# RK05ex6x10.net
KiCad netlist of a schematic drawn in EAGLE
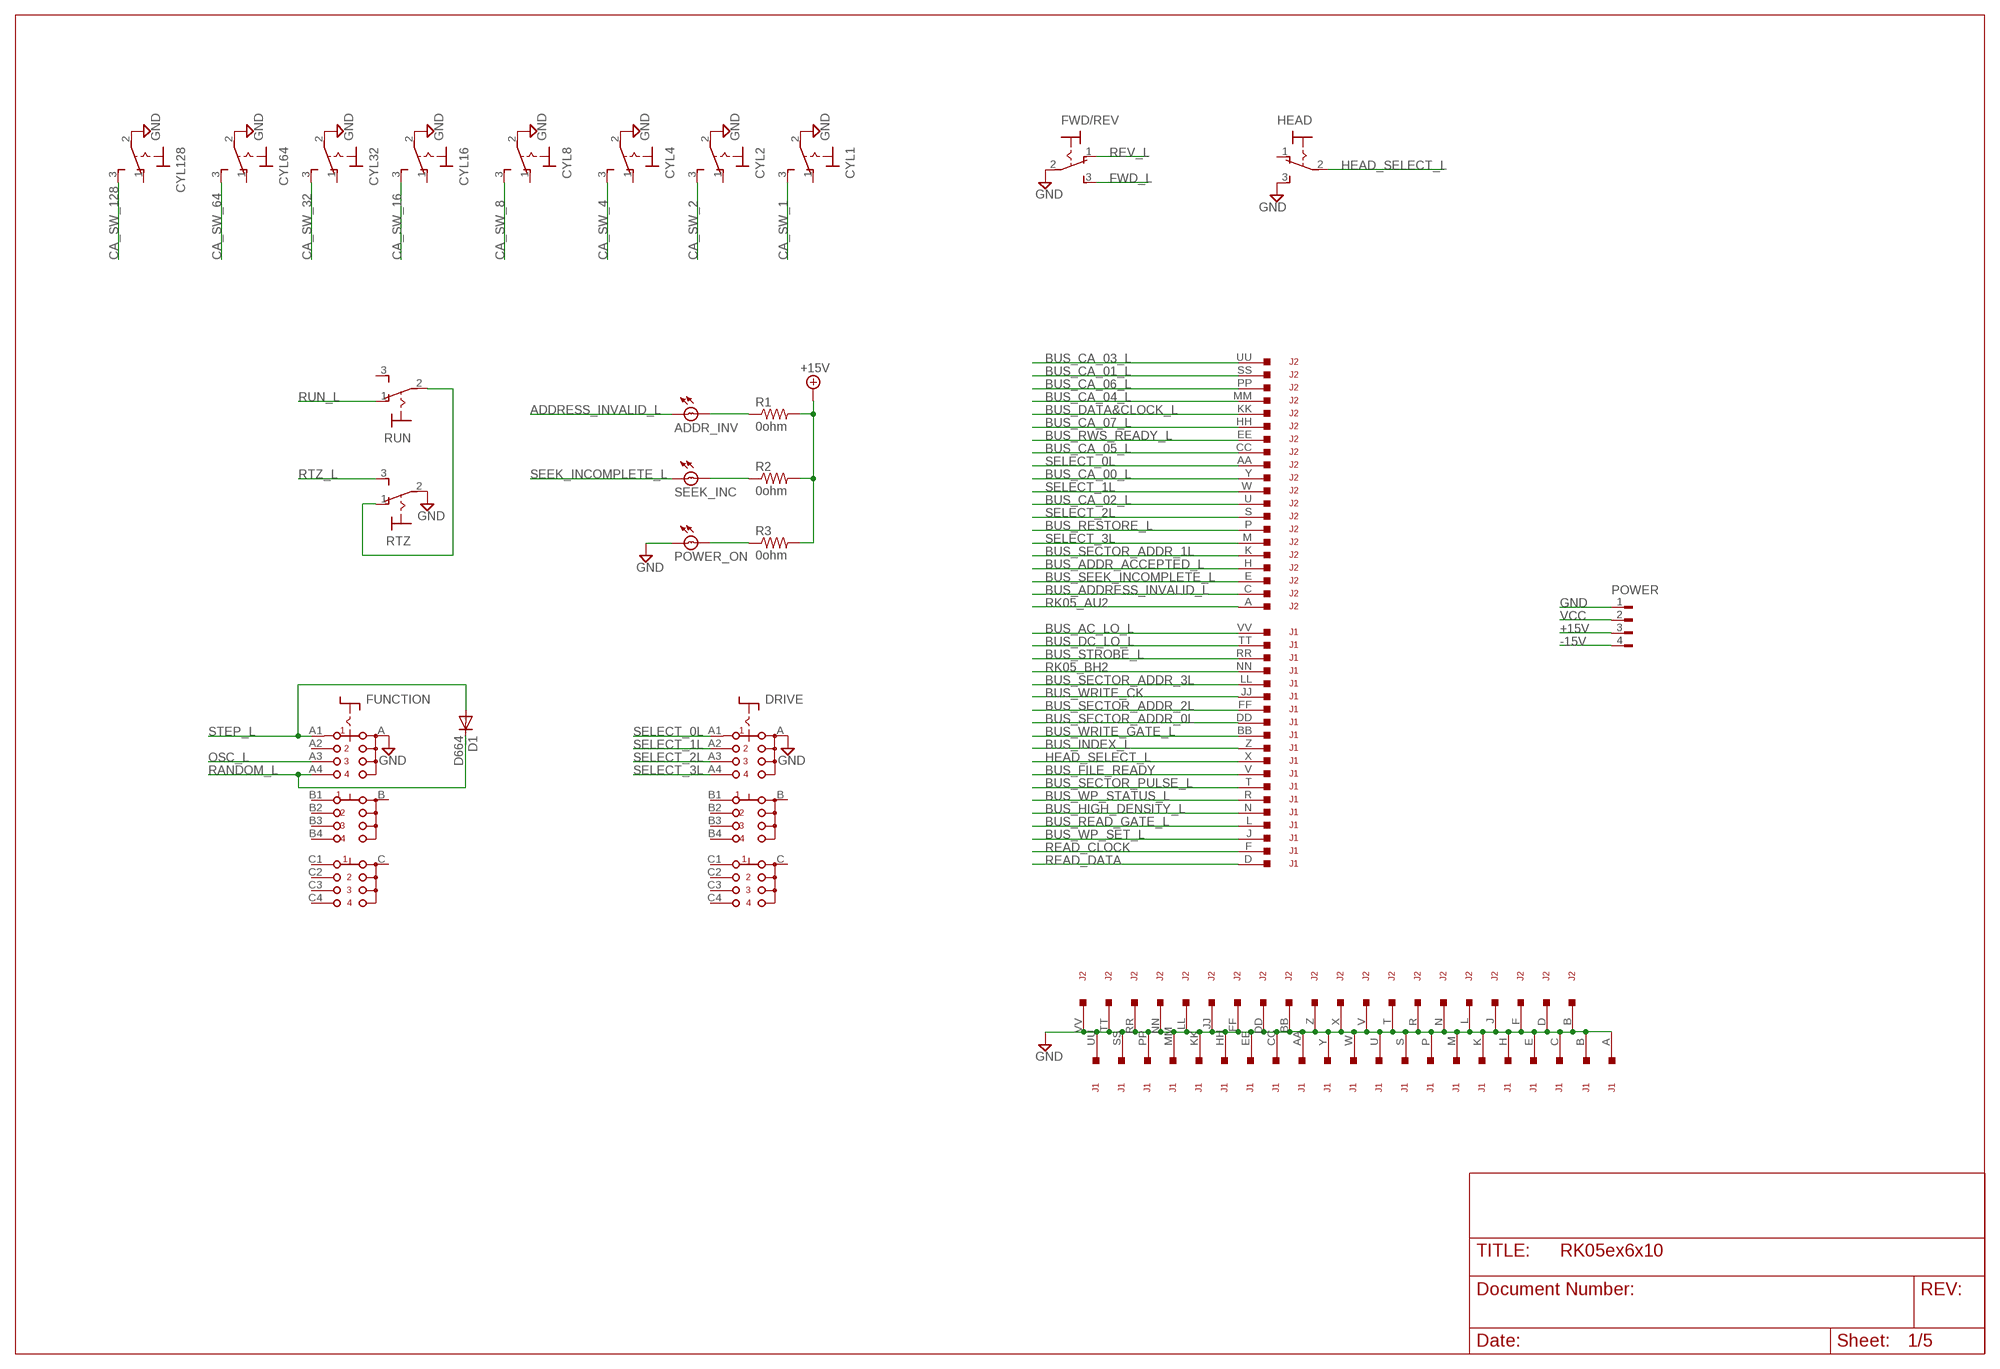
[diagram p0: schematic, sheet 1]
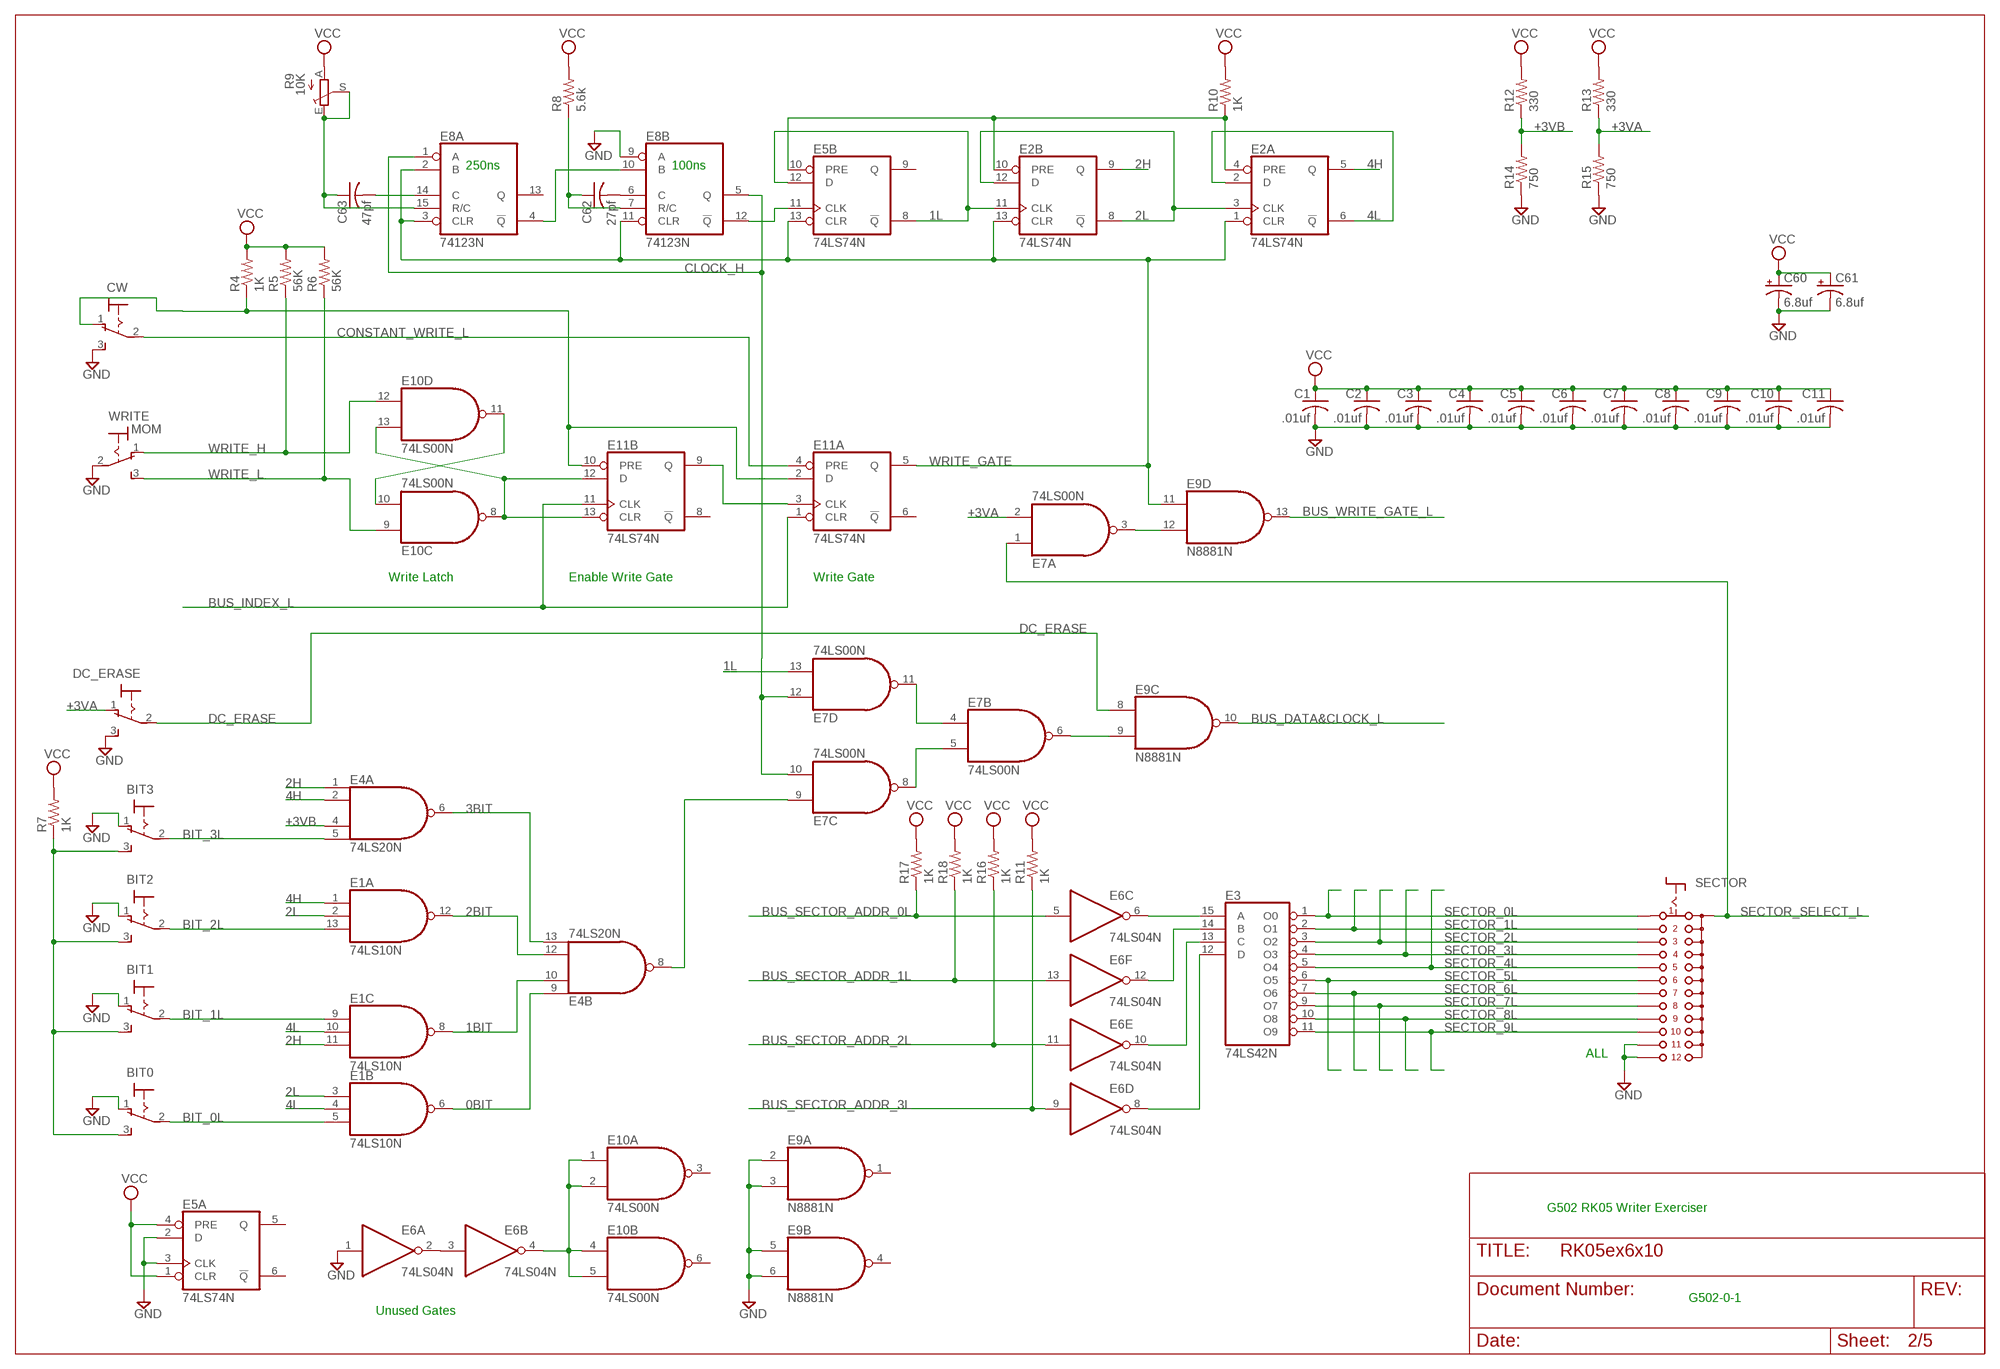
[diagram p1: schematic, sheet 2]
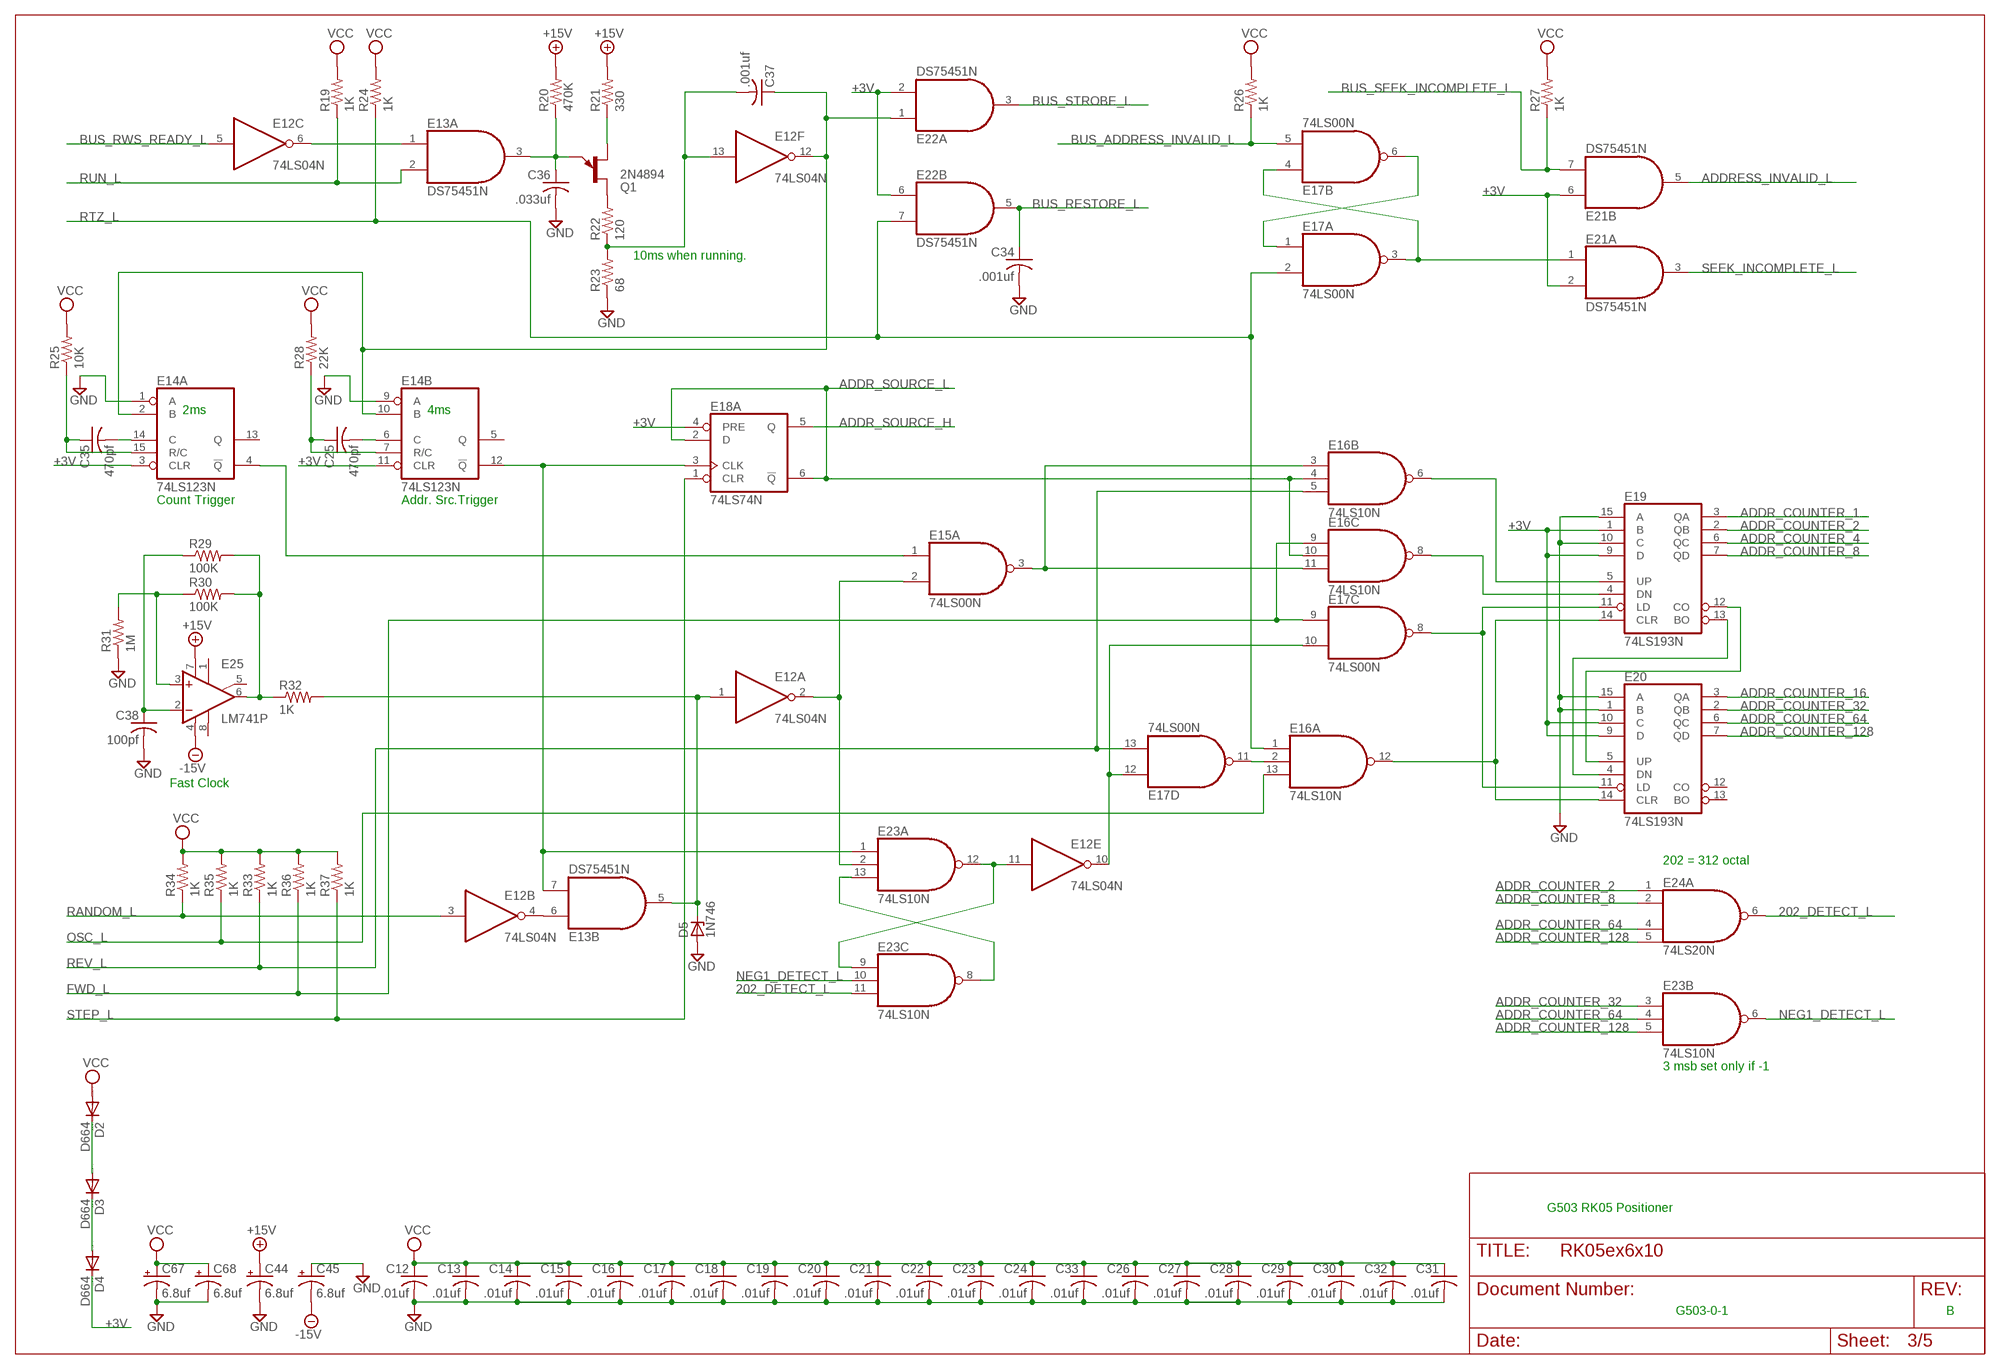
[diagram p2: schematic, sheet 3]
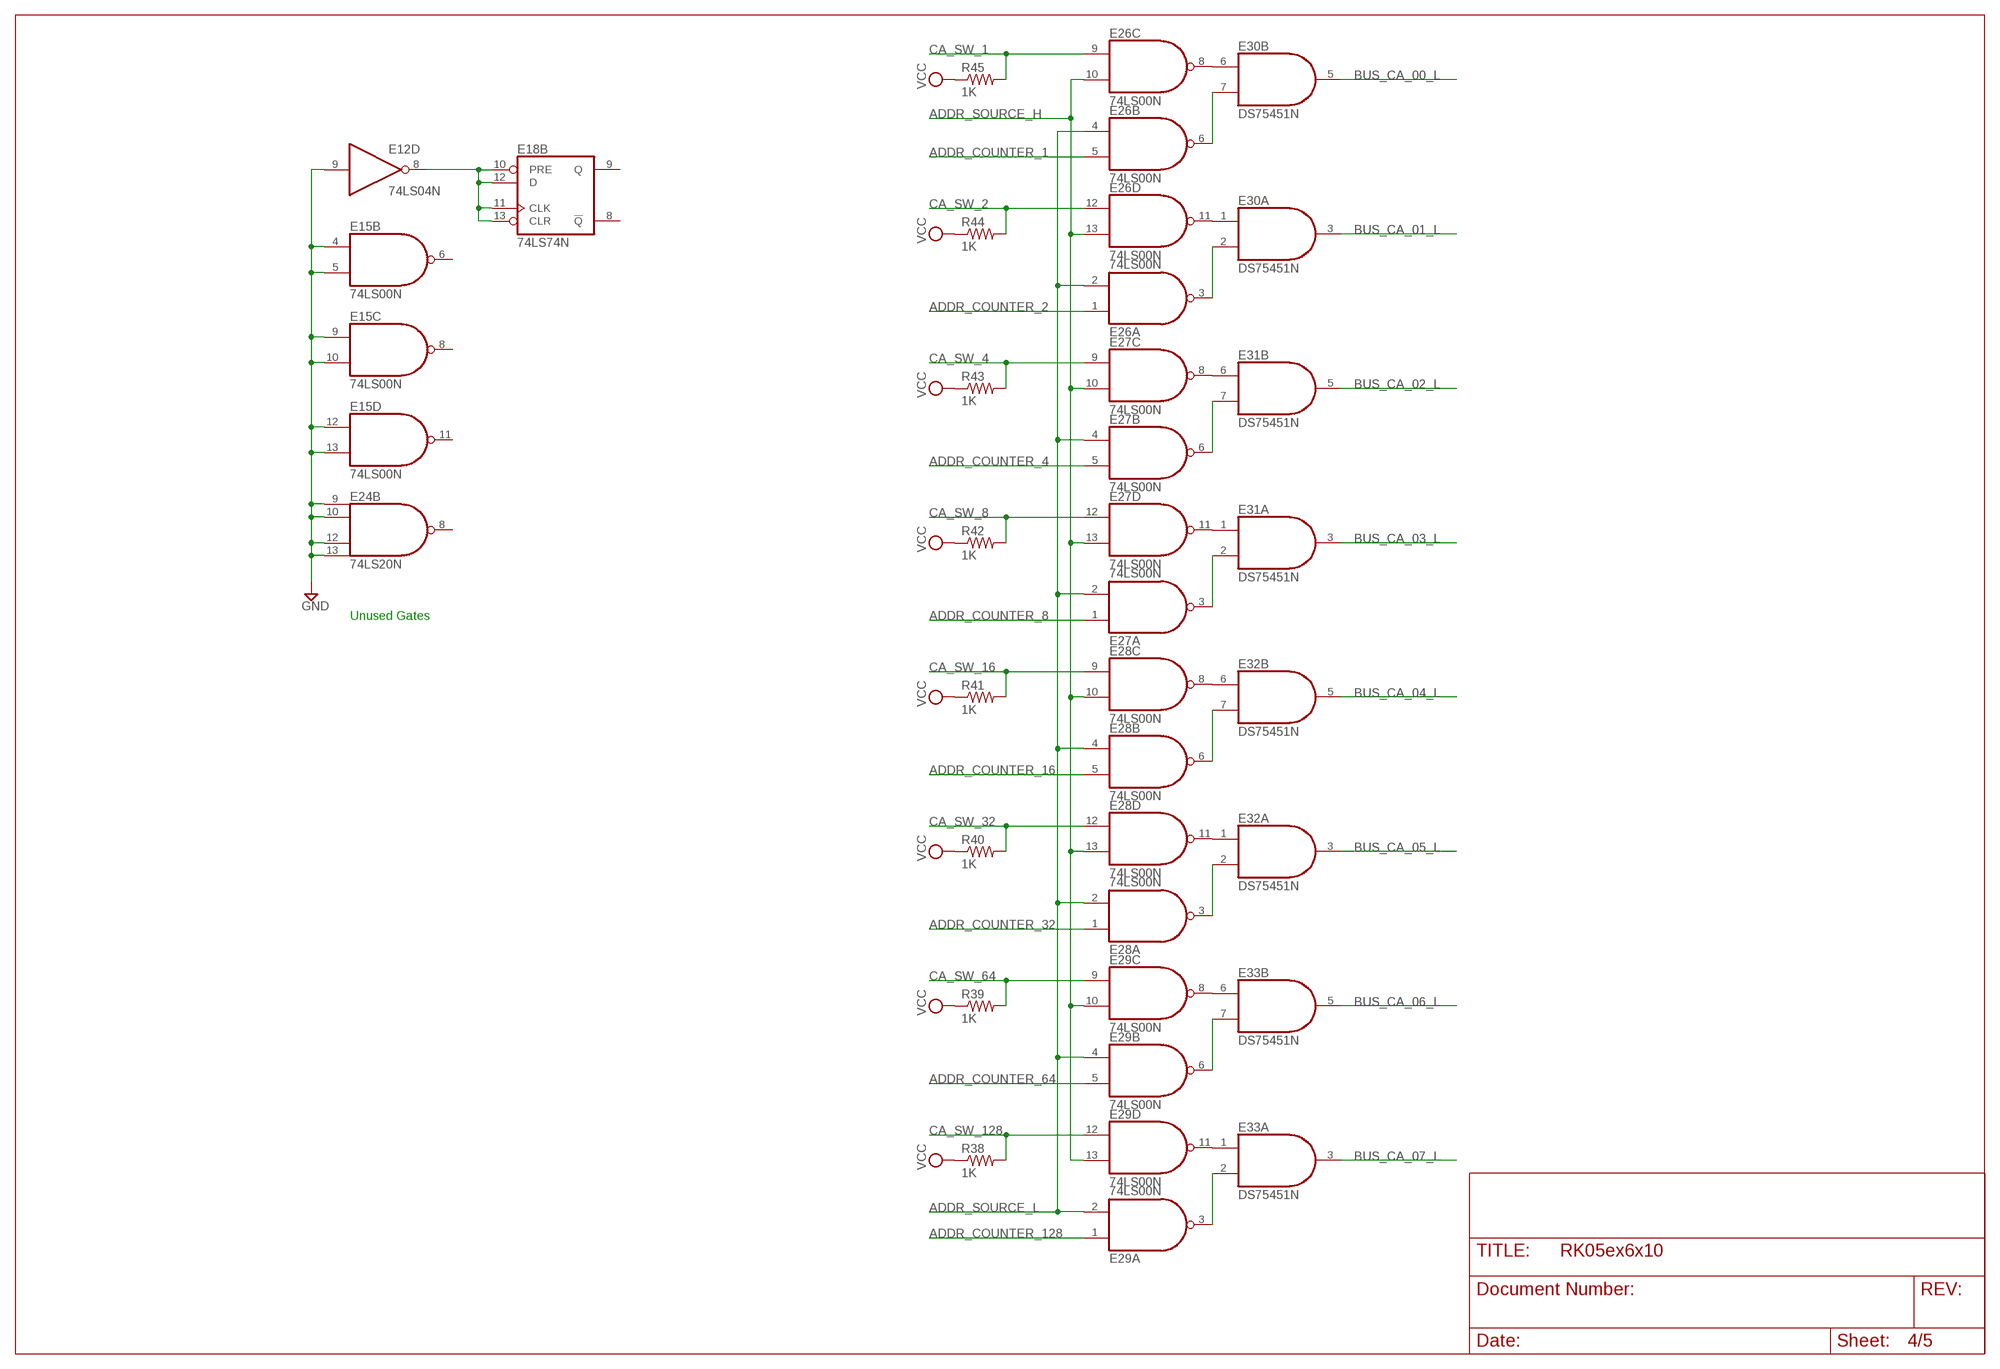
[diagram p3: schematic, sheet 4]
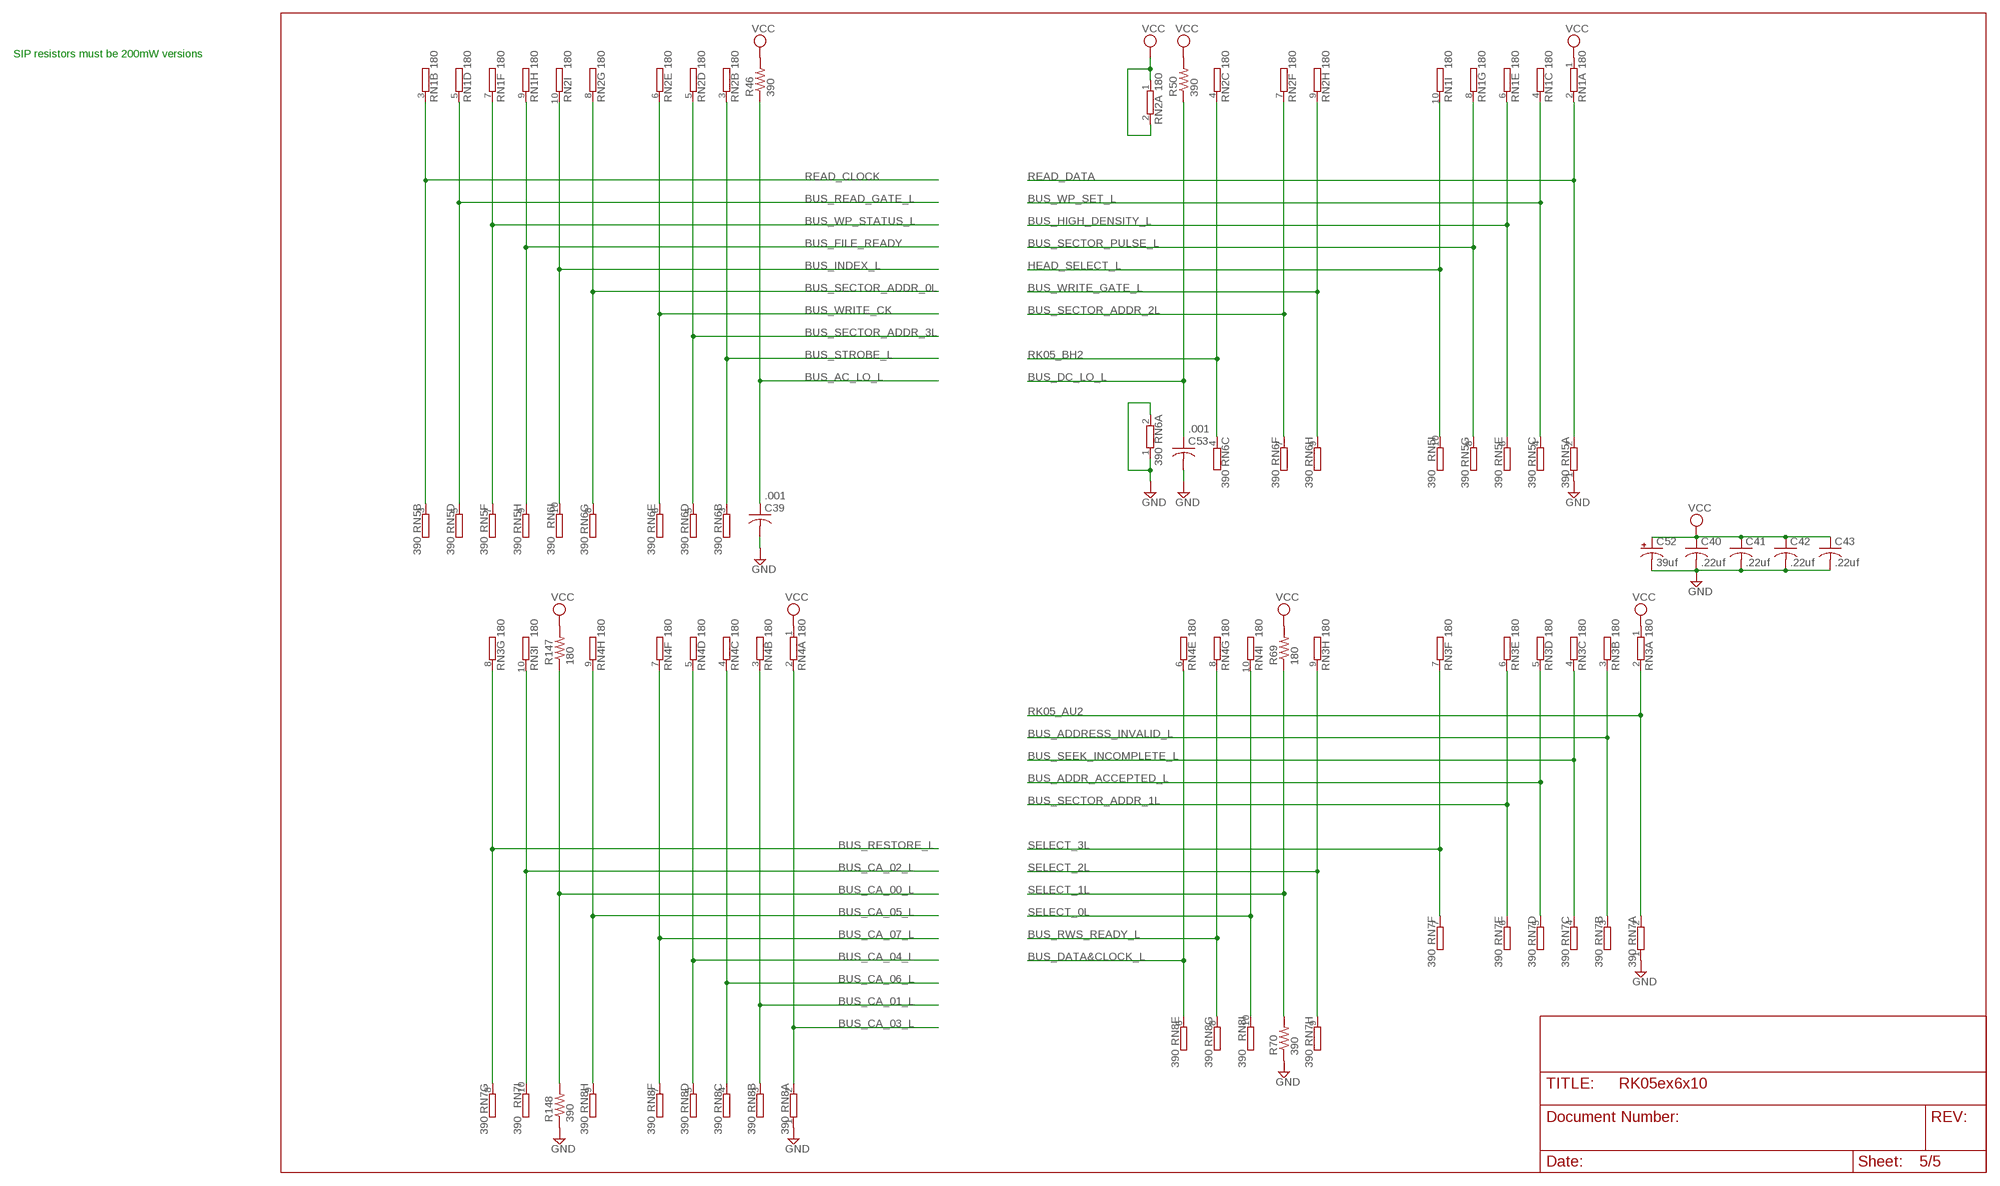
[diagram p4: schematic, sheet 5]

(export (version "E")
  (design (tool "Eeschema 10.0.6"))
  (components
    (comp (ref "BIT0")
      (value "M9040P")
      (footprint "eagle-import:M9040P")
      (libsource (lib "eagle-import") (part "M9040P"))
    )
    (comp (ref "BIT1")
      (value "M9040P")
      (footprint "eagle-import:M9040P")
      (libsource (lib "eagle-import") (part "M9040P"))
    )
    (comp (ref "BIT2")
      (value "M9040P")
      (footprint "eagle-import:M9040P")
      (libsource (lib "eagle-import") (part "M9040P"))
    )
    (comp (ref "BIT3")
      (value "M9040P")
      (footprint "eagle-import:M9040P")
      (libsource (lib "eagle-import") (part "M9040P"))
    )
    (comp (ref "C1")
      (value ".01uf")
      (footprint "eagle-import:C075-032X103")
      (libsource (lib "eagle-import") (part "C-US075-032X103"))
    )
    (comp (ref "C2")
      (value ".01uf")
      (footprint "eagle-import:C075-032X103")
      (libsource (lib "eagle-import") (part "C-US075-032X103"))
    )
    (comp (ref "C3")
      (value ".01uf")
      (footprint "eagle-import:C075-032X103")
      (libsource (lib "eagle-import") (part "C-US075-032X103"))
    )
    (comp (ref "C4")
      (value ".01uf")
      (footprint "eagle-import:C075-032X103")
      (libsource (lib "eagle-import") (part "C-US075-032X103"))
    )
    (comp (ref "C5")
      (value ".01uf")
      (footprint "eagle-import:C075-032X103")
      (libsource (lib "eagle-import") (part "C-US075-032X103"))
    )
    (comp (ref "C6")
      (value ".01uf")
      (footprint "eagle-import:C075-032X103")
      (libsource (lib "eagle-import") (part "C-US075-032X103"))
    )
    (comp (ref "C7")
      (value ".01uf")
      (footprint "eagle-import:C075-032X103")
      (libsource (lib "eagle-import") (part "C-US075-032X103"))
    )
    (comp (ref "C8")
      (value ".01uf")
      (footprint "eagle-import:C075-032X103")
      (libsource (lib "eagle-import") (part "C-US075-032X103"))
    )
    (comp (ref "C9")
      (value ".01uf")
      (footprint "eagle-import:C075-032X103")
      (libsource (lib "eagle-import") (part "C-US075-032X103"))
    )
    (comp (ref "C10")
      (value ".01uf")
      (footprint "eagle-import:C075-032X103")
      (libsource (lib "eagle-import") (part "C-US075-032X103"))
    )
    (comp (ref "C11")
      (value ".01uf")
      (footprint "eagle-import:C075-032X103")
      (libsource (lib "eagle-import") (part "C-US075-032X103"))
    )
    (comp (ref "C60")
      (value "6.8uf")
      (footprint "eagle-import:E15-5")
      (libsource (lib "eagle-import") (part "CPOL-USE15-5AXIAL"))
    )
    (comp (ref "C61")
      (value "6.8uf")
      (footprint "eagle-import:E15-5")
      (libsource (lib "eagle-import") (part "CPOL-USE15-5AXIAL"))
    )
    (comp (ref "C62")
      (value "27pf")
      (footprint "eagle-import:C075-032X103")
      (libsource (lib "eagle-import") (part "C-US075-032X103"))
    )
    (comp (ref "C63")
      (value "47pf")
      (footprint "eagle-import:C075-032X103")
      (libsource (lib "eagle-import") (part "C-US075-032X103"))
    )
    (comp (ref "CW")
      (value "M9040P")
      (footprint "eagle-import:M9040P")
      (libsource (lib "eagle-import") (part "M9040P"))
    )
    (comp (ref "DC_ERASE")
      (value "M9040P")
      (footprint "eagle-import:M9040P")
      (libsource (lib "eagle-import") (part "M9040P"))
    )
    (comp (ref "E1")
      (value "74LS10N")
      (footprint "eagle-import:DIL14")
      (libsource (lib "eagle-import") (part "7410NLS"))
    )
    (comp (ref "E2")
      (value "74LS74N")
      (footprint "eagle-import:DIL14")
      (libsource (lib "eagle-import") (part "7474NLS"))
    )
    (comp (ref "E3")
      (value "74LS42N")
      (footprint "eagle-import:DIL16")
      (libsource (lib "eagle-import") (part "7442NLS"))
    )
    (comp (ref "E4")
      (value "74LS20N")
      (footprint "eagle-import:DIL14")
      (libsource (lib "eagle-import") (part "7420NLS"))
    )
    (comp (ref "E5")
      (value "74LS74N")
      (footprint "eagle-import:DIL14")
      (libsource (lib "eagle-import") (part "7474NLS"))
    )
    (comp (ref "E6")
      (value "74LS04N")
      (footprint "eagle-import:DIL14")
      (libsource (lib "eagle-import") (part "7404NLS"))
    )
    (comp (ref "E7")
      (value "74LS00N")
      (footprint "eagle-import:DIL14")
      (libsource (lib "eagle-import") (part "7400NLS"))
    )
    (comp (ref "E8")
      (value "74123N")
      (footprint "eagle-import:DIL16")
      (libsource (lib "eagle-import") (part "74123NLS"))
    )
    (comp (ref "E9")
      (value "N8881N")
      (footprint "eagle-import:DIL14")
      (libsource (lib "eagle-import") (part "N8881N"))
    )
    (comp (ref "E10")
      (value "74LS00N")
      (footprint "eagle-import:DIL14")
      (libsource (lib "eagle-import") (part "7400NLS"))
    )
    (comp (ref "E11")
      (value "74LS74N")
      (footprint "eagle-import:DIL14")
      (libsource (lib "eagle-import") (part "7474NLS"))
    )
    (comp (ref "R4")
      (value "1K")
      (footprint "eagle-import:0207_10")
      (libsource (lib "eagle-import") (part "R-US_0207/10"))
    )
    (comp (ref "R5")
      (value "56K")
      (footprint "eagle-import:0207_10")
      (libsource (lib "eagle-import") (part "R-US_0207/10"))
    )
    (comp (ref "R6")
      (value "56K")
      (footprint "eagle-import:0207_10")
      (libsource (lib "eagle-import") (part "R-US_0207/10"))
    )
    (comp (ref "R7")
      (value "1K")
      (footprint "eagle-import:0207_10")
      (libsource (lib "eagle-import") (part "R-US_0207/10"))
    )
    (comp (ref "R8")
      (value "5.6k")
      (footprint "eagle-import:0207_10")
      (libsource (lib "eagle-import") (part "R-US_0207/10"))
    )
    (comp (ref "R9")
      (value "10K")
      (footprint "eagle-import:SP19L")
      (libsource (lib "eagle-import") (part "TRIM_EU-B90P"))
    )
    (comp (ref "R10")
      (value "1K")
      (footprint "eagle-import:0207_10")
      (libsource (lib "eagle-import") (part "R-US_0207/10"))
    )
    (comp (ref "R11")
      (value "1K")
      (footprint "eagle-import:0207_10")
      (libsource (lib "eagle-import") (part "R-US_0207/10"))
    )
    (comp (ref "R12")
      (value "330")
      (footprint "eagle-import:0207_10")
      (libsource (lib "eagle-import") (part "R-US_0207/10"))
    )
    (comp (ref "R13")
      (value "330")
      (footprint "eagle-import:0207_10")
      (libsource (lib "eagle-import") (part "R-US_0207/10"))
    )
    (comp (ref "R14")
      (value "750")
      (footprint "eagle-import:0207_10")
      (libsource (lib "eagle-import") (part "R-US_0207/10"))
    )
    (comp (ref "R15")
      (value "750")
      (footprint "eagle-import:0207_10")
      (libsource (lib "eagle-import") (part "R-US_0207/10"))
    )
    (comp (ref "R16")
      (value "1K")
      (footprint "eagle-import:0207_10")
      (libsource (lib "eagle-import") (part "R-US_0207/10"))
    )
    (comp (ref "R17")
      (value "1K")
      (footprint "eagle-import:0207_10")
      (libsource (lib "eagle-import") (part "R-US_0207/10"))
    )
    (comp (ref "R18")
      (value "1K")
      (footprint "eagle-import:0207_10")
      (libsource (lib "eagle-import") (part "R-US_0207/10"))
    )
    (comp (ref "SECTOR")
      (value "CK101X12")
      (footprint "eagle-import:CK101X12")
      (libsource (lib "eagle-import") (part "CK101X12"))
    )
    (comp (ref "WRITE")
      (value "MOM")
      (footprint "eagle-import:M9040P")
      (libsource (lib "eagle-import") (part "M9040P"))
    )
    (comp (ref "C12")
      (value ".01uf")
      (footprint "eagle-import:C075-032X103")
      (libsource (lib "eagle-import") (part "C-US075-032X103"))
    )
    (comp (ref "C13")
      (value ".01uf")
      (footprint "eagle-import:C075-032X103")
      (libsource (lib "eagle-import") (part "C-US075-032X103"))
    )
    (comp (ref "C14")
      (value ".01uf")
      (footprint "eagle-import:C075-032X103")
      (libsource (lib "eagle-import") (part "C-US075-032X103"))
    )
    (comp (ref "C15")
      (value ".01uf")
      (footprint "eagle-import:C075-032X103")
      (libsource (lib "eagle-import") (part "C-US075-032X103"))
    )
    (comp (ref "C16")
      (value ".01uf")
      (footprint "eagle-import:C075-032X103")
      (libsource (lib "eagle-import") (part "C-US075-032X103"))
    )
    (comp (ref "C17")
      (value ".01uf")
      (footprint "eagle-import:C075-032X103")
      (libsource (lib "eagle-import") (part "C-US075-032X103"))
    )
    (comp (ref "C18")
      (value ".01uf")
      (footprint "eagle-import:C075-032X103")
      (libsource (lib "eagle-import") (part "C-US075-032X103"))
    )
    (comp (ref "C19")
      (value ".01uf")
      (footprint "eagle-import:C075-032X103")
      (libsource (lib "eagle-import") (part "C-US075-032X103"))
    )
    (comp (ref "C20")
      (value ".01uf")
      (footprint "eagle-import:C075-032X103")
      (libsource (lib "eagle-import") (part "C-US075-032X103"))
    )
    (comp (ref "C21")
      (value ".01uf")
      (footprint "eagle-import:C075-032X103")
      (libsource (lib "eagle-import") (part "C-US075-032X103"))
    )
    (comp (ref "C22")
      (value ".01uf")
      (footprint "eagle-import:C075-032X103")
      (libsource (lib "eagle-import") (part "C-US075-032X103"))
    )
    (comp (ref "C23")
      (value ".01uf")
      (footprint "eagle-import:C075-032X103")
      (libsource (lib "eagle-import") (part "C-US075-032X103"))
    )
    (comp (ref "C24")
      (value ".01uf")
      (footprint "eagle-import:C075-032X103")
      (libsource (lib "eagle-import") (part "C-US075-032X103"))
    )
    (comp (ref "C25")
      (value "470pf")
      (footprint "eagle-import:C075-032X103")
      (libsource (lib "eagle-import") (part "C-US075-032X103"))
    )
    (comp (ref "C26")
      (value ".01uf")
      (footprint "eagle-import:C075-032X103")
      (libsource (lib "eagle-import") (part "C-US075-032X103"))
    )
    (comp (ref "C27")
      (value ".01uf")
      (footprint "eagle-import:C075-032X103")
      (libsource (lib "eagle-import") (part "C-US075-032X103"))
    )
    (comp (ref "C28")
      (value ".01uf")
      (footprint "eagle-import:C075-032X103")
      (libsource (lib "eagle-import") (part "C-US075-032X103"))
    )
    (comp (ref "C29")
      (value ".01uf")
      (footprint "eagle-import:C075-032X103")
      (libsource (lib "eagle-import") (part "C-US075-032X103"))
    )
    (comp (ref "C30")
      (value ".01uf")
      (footprint "eagle-import:C075-032X103")
      (libsource (lib "eagle-import") (part "C-US075-032X103"))
    )
    (comp (ref "C31")
      (value ".01uf")
      (footprint "eagle-import:C075-032X103")
      (libsource (lib "eagle-import") (part "C-US075-032X103"))
    )
    (comp (ref "C32")
      (value ".01uf")
      (footprint "eagle-import:C075-032X103")
      (libsource (lib "eagle-import") (part "C-US075-032X103"))
    )
    (comp (ref "C33")
      (value ".01uf")
      (footprint "eagle-import:C075-032X103")
      (libsource (lib "eagle-import") (part "C-US075-032X103"))
    )
    (comp (ref "C34")
      (value ".001uf")
      (footprint "eagle-import:C075-032X103")
      (libsource (lib "eagle-import") (part "C-US075-032X103"))
    )
    (comp (ref "C35")
      (value "470pf")
      (footprint "eagle-import:C075-032X103")
      (libsource (lib "eagle-import") (part "C-US075-032X103"))
    )
    (comp (ref "C36")
      (value ".033uf")
      (footprint "eagle-import:C075-032X103")
      (libsource (lib "eagle-import") (part "C-US075-032X103"))
    )
    (comp (ref "C37")
      (value ".001uf")
      (footprint "eagle-import:C075-032X103")
      (libsource (lib "eagle-import") (part "C-US075-032X103"))
    )
    (comp (ref "C38")
      (value "100pf")
      (footprint "eagle-import:C075-032X103")
      (libsource (lib "eagle-import") (part "C-US075-032X103"))
    )
    (comp (ref "C44")
      (value "6.8uf")
      (footprint "eagle-import:E15-5")
      (libsource (lib "eagle-import") (part "CPOL-USE15-5AXIAL"))
    )
    (comp (ref "C45")
      (value "6.8uf")
      (footprint "eagle-import:E15-5")
      (libsource (lib "eagle-import") (part "CPOL-USE15-5AXIAL"))
    )
    (comp (ref "C67")
      (value "6.8uf")
      (footprint "eagle-import:E15-5")
      (libsource (lib "eagle-import") (part "CPOL-USE15-5AXIAL"))
    )
    (comp (ref "C68")
      (value "6.8uf")
      (footprint "eagle-import:E15-5")
      (libsource (lib "eagle-import") (part "CPOL-USE15-5AXIAL"))
    )
    (comp (ref "D2")
      (value "D664")
      (footprint "eagle-import:DO35-10")
      (libsource (lib "eagle-import") (part "1N4148DO35-10"))
    )
    (comp (ref "D3")
      (value "D664")
      (footprint "eagle-import:DO35-10")
      (libsource (lib "eagle-import") (part "1N4148DO35-10"))
    )
    (comp (ref "D4")
      (value "D664")
      (footprint "eagle-import:DO35-10")
      (libsource (lib "eagle-import") (part "1N4148DO35-10"))
    )
    (comp (ref "D5")
      (value "1N746")
      (footprint "eagle-import:DO35Z10")
      (libsource (lib "eagle-import") (part "ZENER-DIODEDO35Z10"))
    )
    (comp (ref "E12")
      (value "74LS04N")
      (footprint "eagle-import:DIL14")
      (libsource (lib "eagle-import") (part "7404NLS"))
    )
    (comp (ref "E13")
      (value "DS75451N")
      (footprint "eagle-import:DIL08")
      (libsource (lib "eagle-import") (part "DS75451N"))
    )
    (comp (ref "E14")
      (value "74LS123N")
      (footprint "eagle-import:DIL16")
      (libsource (lib "eagle-import") (part "74123NLS"))
    )
    (comp (ref "E15")
      (value "74LS00N")
      (footprint "eagle-import:DIL14")
      (libsource (lib "eagle-import") (part "7400NLS"))
    )
    (comp (ref "E16")
      (value "74LS10N")
      (footprint "eagle-import:DIL14")
      (libsource (lib "eagle-import") (part "7410NAS"))
    )
    (comp (ref "E17")
      (value "74LS00N")
      (footprint "eagle-import:DIL14")
      (libsource (lib "eagle-import") (part "7400NLS"))
    )
    (comp (ref "E18")
      (value "74LS74N")
      (footprint "eagle-import:DIL14")
      (libsource (lib "eagle-import") (part "7474NLS"))
    )
    (comp (ref "E19")
      (value "74LS193N")
      (footprint "eagle-import:DIL16")
      (libsource (lib "eagle-import") (part "74193NLS"))
    )
    (comp (ref "E20")
      (value "74LS193N")
      (footprint "eagle-import:DIL16")
      (libsource (lib "eagle-import") (part "74193NLS"))
    )
    (comp (ref "E21")
      (value "DS75451N")
      (footprint "eagle-import:DIL08")
      (libsource (lib "eagle-import") (part "DS75451N"))
    )
    (comp (ref "E22")
      (value "DS75451N")
      (footprint "eagle-import:DIL08")
      (libsource (lib "eagle-import") (part "DS75451N"))
    )
    (comp (ref "E23")
      (value "74LS10N")
      (footprint "eagle-import:DIL14")
      (libsource (lib "eagle-import") (part "7410NAS"))
    )
    (comp (ref "E24")
      (value "74LS20N")
      (footprint "eagle-import:DIL14")
      (libsource (lib "eagle-import") (part "7420NLS"))
    )
    (comp (ref "E25")
      (value "LM741P")
      (footprint "eagle-import:DIL08")
      (libsource (lib "eagle-import") (part "741PLM"))
    )
    (comp (ref "Q1")
      (value "2N4894")
      (footprint "eagle-import:TO92E")
      (libsource (lib "eagle-import") (part "2N4870"))
    )
    (comp (ref "R19")
      (value "1K")
      (footprint "eagle-import:0207_10")
      (libsource (lib "eagle-import") (part "R-US_0207/10"))
    )
    (comp (ref "R20")
      (value "470K")
      (footprint "eagle-import:0207_10")
      (libsource (lib "eagle-import") (part "R-US_0207/10"))
    )
    (comp (ref "R21")
      (value "330")
      (footprint "eagle-import:0207_10")
      (libsource (lib "eagle-import") (part "R-US_0207/10"))
    )
    (comp (ref "R22")
      (value "120")
      (footprint "eagle-import:0207_10")
      (libsource (lib "eagle-import") (part "R-US_0207/10"))
    )
    (comp (ref "R23")
      (value "68")
      (footprint "eagle-import:0207_10")
      (libsource (lib "eagle-import") (part "R-US_0207/10"))
    )
    (comp (ref "R24")
      (value "1K")
      (footprint "eagle-import:0207_10")
      (libsource (lib "eagle-import") (part "R-US_0207/10"))
    )
    (comp (ref "R25")
      (value "10K")
      (footprint "eagle-import:0207_10")
      (libsource (lib "eagle-import") (part "R-US_0207/10"))
    )
    (comp (ref "R26")
      (value "1K")
      (footprint "eagle-import:0207_10")
      (libsource (lib "eagle-import") (part "R-US_0207/10"))
    )
    (comp (ref "R27")
      (value "1K")
      (footprint "eagle-import:0207_10")
      (libsource (lib "eagle-import") (part "R-US_0207/10"))
    )
    (comp (ref "R28")
      (value "22K")
      (footprint "eagle-import:0207_10")
      (libsource (lib "eagle-import") (part "R-US_0207/10"))
    )
    (comp (ref "R29")
      (value "100K")
      (footprint "eagle-import:0207_10")
      (libsource (lib "eagle-import") (part "R-US_0207/10"))
    )
    (comp (ref "R30")
      (value "100K")
      (footprint "eagle-import:0207_10")
      (libsource (lib "eagle-import") (part "R-US_0207/10"))
    )
    (comp (ref "R31")
      (value "1M")
      (footprint "eagle-import:0207_10")
      (libsource (lib "eagle-import") (part "R-US_0207/10"))
    )
    (comp (ref "R32")
      (value "1K")
      (footprint "eagle-import:0207_10")
      (libsource (lib "eagle-import") (part "R-US_0207/10"))
    )
    (comp (ref "R33")
      (value "1K")
      (footprint "eagle-import:0207_10")
      (libsource (lib "eagle-import") (part "R-US_0207/10"))
    )
    (comp (ref "R34")
      (value "1K")
      (footprint "eagle-import:0207_10")
      (libsource (lib "eagle-import") (part "R-US_0207/10"))
    )
    (comp (ref "R35")
      (value "1K")
      (footprint "eagle-import:0207_10")
      (libsource (lib "eagle-import") (part "R-US_0207/10"))
    )
    (comp (ref "R36")
      (value "1K")
      (footprint "eagle-import:0207_10")
      (libsource (lib "eagle-import") (part "R-US_0207/10"))
    )
    (comp (ref "R37")
      (value "1K")
      (footprint "eagle-import:0207_10")
      (libsource (lib "eagle-import") (part "R-US_0207/10"))
    )
    (comp (ref "E26")
      (value "74LS00N")
      (footprint "eagle-import:DIL14")
      (libsource (lib "eagle-import") (part "7400NLS"))
    )
    (comp (ref "E27")
      (value "74LS00N")
      (footprint "eagle-import:DIL14")
      (libsource (lib "eagle-import") (part "7400NLS"))
    )
    (comp (ref "E28")
      (value "74LS00N")
      (footprint "eagle-import:DIL14")
      (libsource (lib "eagle-import") (part "7400NLS"))
    )
    (comp (ref "E29")
      (value "74LS00N")
      (footprint "eagle-import:DIL14")
      (libsource (lib "eagle-import") (part "7400NLS"))
    )
    (comp (ref "E30")
      (value "DS75451N")
      (footprint "eagle-import:DIL08")
      (libsource (lib "eagle-import") (part "DS75451N"))
    )
    (comp (ref "E31")
      (value "DS75451N")
      (footprint "eagle-import:DIL08")
      (libsource (lib "eagle-import") (part "DS75451N"))
    )
    (comp (ref "E32")
      (value "DS75451N")
      (footprint "eagle-import:DIL08")
      (libsource (lib "eagle-import") (part "DS75451N"))
    )
    (comp (ref "E33")
      (value "DS75451N")
      (footprint "eagle-import:DIL08")
      (libsource (lib "eagle-import") (part "DS75451N"))
    )
    (comp (ref "R38")
      (value "1K")
      (footprint "eagle-import:0207_10")
      (libsource (lib "eagle-import") (part "R-US_0207/10"))
    )
    (comp (ref "R39")
      (value "1K")
      (footprint "eagle-import:0207_10")
      (libsource (lib "eagle-import") (part "R-US_0207/10"))
    )
    (comp (ref "R40")
      (value "1K")
      (footprint "eagle-import:0207_10")
      (libsource (lib "eagle-import") (part "R-US_0207/10"))
    )
    (comp (ref "R41")
      (value "1K")
      (footprint "eagle-import:0207_10")
      (libsource (lib "eagle-import") (part "R-US_0207/10"))
    )
    (comp (ref "R42")
      (value "1K")
      (footprint "eagle-import:0207_10")
      (libsource (lib "eagle-import") (part "R-US_0207/10"))
    )
    (comp (ref "R43")
      (value "1K")
      (footprint "eagle-import:0207_10")
      (libsource (lib "eagle-import") (part "R-US_0207/10"))
    )
    (comp (ref "R44")
      (value "1K")
      (footprint "eagle-import:0207_10")
      (libsource (lib "eagle-import") (part "R-US_0207/10"))
    )
    (comp (ref "R45")
      (value "1K")
      (footprint "eagle-import:0207_10")
      (libsource (lib "eagle-import") (part "R-US_0207/10"))
    )
    (comp (ref "ADDR_INV")
      (value "BULB")
      (footprint "eagle-import:BULB")
      (libsource (lib "eagle-import") (part "BULB"))
    )
    (comp (ref "CYL1")
      (value "M9040P")
      (footprint "eagle-import:M9040P")
      (libsource (lib "eagle-import") (part "M9040P"))
    )
    (comp (ref "CYL2")
      (value "M9040P")
      (footprint "eagle-import:M9040P")
      (libsource (lib "eagle-import") (part "M9040P"))
    )
    (comp (ref "CYL4")
      (value "M9040P")
      (footprint "eagle-import:M9040P")
      (libsource (lib "eagle-import") (part "M9040P"))
    )
    (comp (ref "CYL8")
      (value "M9040P")
      (footprint "eagle-import:M9040P")
      (libsource (lib "eagle-import") (part "M9040P"))
    )
    (comp (ref "CYL16")
      (value "M9040P")
      (footprint "eagle-import:M9040P")
      (libsource (lib "eagle-import") (part "M9040P"))
    )
    (comp (ref "CYL32")
      (value "M9040P")
      (footprint "eagle-import:M9040P")
      (libsource (lib "eagle-import") (part "M9040P"))
    )
    (comp (ref "CYL64")
      (value "M9040P")
      (footprint "eagle-import:M9040P")
      (libsource (lib "eagle-import") (part "M9040P"))
    )
    (comp (ref "CYL128")
      (value "M9040P")
      (footprint "eagle-import:M9040P")
      (libsource (lib "eagle-import") (part "M9040P"))
    )
    (comp (ref "D1")
      (value "D664")
      (footprint "eagle-import:DO35-10")
      (libsource (lib "eagle-import") (part "1N4148DO35-10"))
    )
    (comp (ref "DRIVE")
      (value "CK103X04")
      (footprint "eagle-import:CK103X04")
      (libsource (lib "eagle-import") (part "CK103X04"))
    )
    (comp (ref "FUNCTION")
      (value "CK103X04")
      (footprint "eagle-import:CK103X04")
      (libsource (lib "eagle-import") (part "CK103X04"))
    )
    (comp (ref "FWD/REV")
      (value "M9040P")
      (footprint "eagle-import:M9040P")
      (libsource (lib "eagle-import") (part "M9040P"))
    )
    (comp (ref "HEAD")
      (value "M9040P")
      (footprint "eagle-import:M9040P")
      (libsource (lib "eagle-import") (part "M9040P"))
    )
    (comp (ref "J1")
      (value "DEC40PINSV")
      (footprint "eagle-import:DEC40PINV")
      (libsource (lib "eagle-import") (part "DEC40PINSV"))
    )
    (comp (ref "J2")
      (value "DEC40PINSV")
      (footprint "eagle-import:DEC40PINV")
      (libsource (lib "eagle-import") (part "DEC40PINSV"))
    )
    (comp (ref "POWER")
      (value "FLOPPY-4")
      (footprint "eagle-import:FLOPPY-4")
      (libsource (lib "eagle-import") (part "FLOPPY-4"))
    )
    (comp (ref "POWER_ON")
      (value "BULB")
      (footprint "eagle-import:BULB")
      (libsource (lib "eagle-import") (part "BULB"))
    )
    (comp (ref "R1")
      (value "0ohm")
      (footprint "eagle-import:0207_10")
      (libsource (lib "eagle-import") (part "R-US_0207/10"))
    )
    (comp (ref "R2")
      (value "0ohm")
      (footprint "eagle-import:0207_10")
      (libsource (lib "eagle-import") (part "R-US_0207/10"))
    )
    (comp (ref "R3")
      (value "0ohm")
      (footprint "eagle-import:0207_10")
      (libsource (lib "eagle-import") (part "R-US_0207/10"))
    )
    (comp (ref "RTZ")
      (value "M9040P")
      (footprint "eagle-import:M9040P")
      (libsource (lib "eagle-import") (part "M9040P"))
    )
    (comp (ref "RUN")
      (value "M9040P")
      (footprint "eagle-import:M9040P")
      (libsource (lib "eagle-import") (part "M9040P"))
    )
    (comp (ref "SEEK_INC")
      (value "BULB")
      (footprint "eagle-import:BULB")
      (libsource (lib "eagle-import") (part "BULB"))
    )
    (comp (ref "C39")
      (value ".001")
      (footprint "eagle-import:C050-025X075")
      (libsource (lib "eagle-import") (part "C-US050-025X075"))
    )
    (comp (ref "C40")
      (value ".22uf")
      (footprint "eagle-import:C050-025X075")
      (libsource (lib "eagle-import") (part "C-US050-025X075"))
    )
    (comp (ref "C41")
      (value ".22uf")
      (footprint "eagle-import:C050-025X075")
      (libsource (lib "eagle-import") (part "C-US050-025X075"))
    )
    (comp (ref "C42")
      (value ".22uf")
      (footprint "eagle-import:C050-025X075")
      (libsource (lib "eagle-import") (part "C-US050-025X075"))
    )
    (comp (ref "C43")
      (value ".22uf")
      (footprint "eagle-import:C050-025X075")
      (libsource (lib "eagle-import") (part "C-US050-025X075"))
    )
    (comp (ref "C52")
      (value "39uf")
      (footprint "eagle-import:E15-5")
      (libsource (lib "eagle-import") (part "CPOL-USE15-5AXIAL"))
    )
    (comp (ref "C53")
      (value ".001")
      (footprint "eagle-import:C050-025X075")
      (libsource (lib "eagle-import") (part "C-US050-025X075"))
    )
    (comp (ref "R46")
      (value "390")
      (footprint "eagle-import:0207_10")
      (libsource (lib "eagle-import") (part "R-US_0207/10"))
    )
    (comp (ref "R50")
      (value "390")
      (footprint "eagle-import:0207_10")
      (libsource (lib "eagle-import") (part "R-US_0207/10"))
    )
    (comp (ref "R69")
      (value "180")
      (footprint "eagle-import:0207_10")
      (libsource (lib "eagle-import") (part "R-US_0207/10"))
    )
    (comp (ref "R70")
      (value "390")
      (footprint "eagle-import:0207_10")
      (libsource (lib "eagle-import") (part "R-US_0207/10"))
    )
    (comp (ref "R147")
      (value "180")
      (footprint "eagle-import:0207_10")
      (libsource (lib "eagle-import") (part "R-US_0207/10"))
    )
    (comp (ref "R148")
      (value "390")
      (footprint "eagle-import:0207_10")
      (libsource (lib "eagle-import") (part "R-US_0207/10"))
    )
    (comp (ref "RN1")
      (value "180")
      (footprint "eagle-import:SIL10")
      (libsource (lib "eagle-import") (part "GE09R"))
    )
    (comp (ref "RN2")
      (value "180")
      (footprint "eagle-import:SIL10")
      (libsource (lib "eagle-import") (part "GE09R"))
    )
    (comp (ref "RN3")
      (value "180")
      (footprint "eagle-import:SIL10")
      (libsource (lib "eagle-import") (part "GE09R"))
    )
    (comp (ref "RN4")
      (value "180")
      (footprint "eagle-import:SIL10")
      (libsource (lib "eagle-import") (part "GE09R"))
    )
    (comp (ref "RN5")
      (value "390")
      (footprint "eagle-import:SIL10")
      (libsource (lib "eagle-import") (part "GE09R"))
    )
    (comp (ref "RN6")
      (value "390")
      (footprint "eagle-import:SIL10")
      (libsource (lib "eagle-import") (part "GE09R"))
    )
    (comp (ref "RN7")
      (value "390")
      (footprint "eagle-import:SIL10")
      (libsource (lib "eagle-import") (part "GE09R"))
    )
    (comp (ref "RN8")
      (value "390")
      (footprint "eagle-import:SIL10")
      (libsource (lib "eagle-import") (part "GE09R"))
    )
  )
  (nets
    (net (code "1") (name "+3V") (class "Default")
      (node (ref "D4") (pin "C") (pinfunction "C_C") (pintype "passive"))
      (node (ref "E14") (pin "11") (pinfunction "CLR_11") (pintype "input"))
      (node (ref "E14") (pin "3") (pinfunction "CLR_3") (pintype "input"))
      (node (ref "E18") (pin "4") (pinfunction "PRE_4") (pintype "input"))
      (node (ref "E19") (pin "1") (pinfunction "B_1") (pintype "input"))
      (node (ref "E19") (pin "9") (pinfunction "D_9") (pintype "input"))
      (node (ref "E20") (pin "10") (pinfunction "C_10") (pintype "input"))
      (node (ref "E20") (pin "9") (pinfunction "D_9") (pintype "input"))
      (node (ref "E21") (pin "2") (pinfunction "I1_2") (pintype "input"))
      (node (ref "E21") (pin "6") (pinfunction "I0_6") (pintype "input"))
      (node (ref "E22") (pin "2") (pinfunction "I1_2") (pintype "input"))
      (node (ref "E22") (pin "6") (pinfunction "I0_6") (pintype "input"))
    )
    (net (code "2") (name "+3VA") (class "Default")
      (node (ref "DC_ERASE") (pin "1") (pinfunction "O_1") (pintype "passive"))
      (node (ref "E7") (pin "2") (pinfunction "I1_2") (pintype "input"))
      (node (ref "R13") (pin "1") (pinfunction "1_1") (pintype "passive"))
      (node (ref "R15") (pin "2") (pinfunction "2_2") (pintype "passive"))
    )
    (net (code "3") (name "+3VB") (class "Default")
      (node (ref "E4") (pin "4") (pinfunction "I2_4") (pintype "input"))
      (node (ref "R12") (pin "1") (pinfunction "1_1") (pintype "passive"))
      (node (ref "R14") (pin "2") (pinfunction "2_2") (pintype "passive"))
    )
    (net (code "4") (name "+15V") (class "Default")
      (node (ref "C44") (pin "+") (pinfunction "+_+") (pintype "passive"))
      (node (ref "E25") (pin "7") (pinfunction "V+_7") (pintype "power_in"))
      (node (ref "POWER") (pin "3") (pinfunction "3_3") (pintype "passive"))
      (node (ref "R1") (pin "2") (pinfunction "2_2") (pintype "passive"))
      (node (ref "R2") (pin "2") (pinfunction "2_2") (pintype "passive"))
      (node (ref "R20") (pin "2") (pinfunction "2_2") (pintype "passive"))
      (node (ref "R21") (pin "2") (pinfunction "2_2") (pintype "passive"))
      (node (ref "R3") (pin "2") (pinfunction "2_2") (pintype "passive"))
    )
    (net (code "5") (name "-15V") (class "Default")
      (node (ref "C45") (pin "-") (pinfunction "-_-") (pintype "passive"))
      (node (ref "E25") (pin "4") (pinfunction "V-_4") (pintype "power_in"))
      (node (ref "POWER") (pin "4") (pinfunction "4_4") (pintype "passive"))
    )
    (net (code "6") (name "0BIT") (class "Default")
      (node (ref "E1") (pin "6") (pinfunction "O_6") (pintype "output"))
      (node (ref "E4") (pin "9") (pinfunction "I0_9") (pintype "input"))
    )
    (net (code "7") (name "1BIT") (class "Default")
      (node (ref "E1") (pin "8") (pinfunction "O_8") (pintype "output"))
      (node (ref "E4") (pin "10") (pinfunction "I1_10") (pintype "input"))
    )
    (net (code "8") (name "1L") (class "Default")
      (node (ref "E2") (pin "11") (pinfunction "CLK_11") (pintype "input"))
      (node (ref "E5") (pin "12") (pinfunction "D_12") (pintype "input"))
      (node (ref "E5") (pin "8") (pinfunction "~{Q}_8") (pintype "output"))
      (node (ref "E7") (pin "13") (pinfunction "I1_13") (pintype "input"))
    )
    (net (code "9") (name "2BIT") (class "Default")
      (node (ref "E1") (pin "12") (pinfunction "O_12") (pintype "output"))
      (node (ref "E4") (pin "12") (pinfunction "I2_12") (pintype "input"))
    )
    (net (code "10") (name "2H") (class "Default")
      (node (ref "E1") (pin "11") (pinfunction "I2_11") (pintype "input"))
      (node (ref "E2") (pin "9") (pinfunction "Q_9") (pintype "output"))
      (node (ref "E4") (pin "1") (pinfunction "I0_1") (pintype "input"))
    )
    (net (code "11") (name "2L") (class "Default")
      (node (ref "E1") (pin "2") (pinfunction "I1_2") (pintype "input"))
      (node (ref "E1") (pin "3") (pinfunction "I0_3") (pintype "input"))
      (node (ref "E2") (pin "12") (pinfunction "D_12") (pintype "input"))
      (node (ref "E2") (pin "3") (pinfunction "CLK_3") (pintype "input"))
      (node (ref "E2") (pin "8") (pinfunction "~{Q}_8") (pintype "output"))
    )
    (net (code "12") (name "3BIT") (class "Default")
      (node (ref "E4") (pin "13") (pinfunction "I3_13") (pintype "input"))
      (node (ref "E4") (pin "6") (pinfunction "O_6") (pintype "output"))
    )
    (net (code "13") (name "4H") (class "Default")
      (node (ref "E1") (pin "1") (pinfunction "I0_1") (pintype "input"))
      (node (ref "E2") (pin "5") (pinfunction "Q_5") (pintype "output"))
      (node (ref "E4") (pin "2") (pinfunction "I1_2") (pintype "input"))
    )
    (net (code "14") (name "4L") (class "Default")
      (node (ref "E1") (pin "10") (pinfunction "I1_10") (pintype "input"))
      (node (ref "E1") (pin "4") (pinfunction "I1_4") (pintype "input"))
      (node (ref "E2") (pin "2") (pinfunction "D_2") (pintype "input"))
      (node (ref "E2") (pin "6") (pinfunction "~{Q}_6") (pintype "output"))
    )
    (net (code "15") (name "202_DETECT_L") (class "Default")
      (node (ref "E23") (pin "11") (pinfunction "I2_11") (pintype "input"))
      (node (ref "E24") (pin "6") (pinfunction "O_6") (pintype "output"))
    )
    (net (code "16") (name "ADDRESS_INVALID_L") (class "Default")
      (node (ref "ADDR_INV") (pin "B") (pinfunction "B_B") (pintype "passive"))
      (node (ref "E21") (pin "5") (pinfunction "O_5") (pintype "open_collector"))
    )
    (net (code "17") (name "ADDR_COUNTER_1") (class "Default")
      (node (ref "E19") (pin "3") (pinfunction "QA_3") (pintype "output"))
      (node (ref "E26") (pin "5") (pinfunction "I1_5") (pintype "input"))
    )
    (net (code "18") (name "ADDR_COUNTER_2") (class "Default")
      (node (ref "E19") (pin "2") (pinfunction "QB_2") (pintype "output"))
      (node (ref "E24") (pin "1") (pinfunction "I0_1") (pintype "input"))
      (node (ref "E26") (pin "1") (pinfunction "I0_1") (pintype "input"))
    )
    (net (code "19") (name "ADDR_COUNTER_4") (class "Default")
      (node (ref "E19") (pin "6") (pinfunction "QC_6") (pintype "output"))
      (node (ref "E27") (pin "5") (pinfunction "I1_5") (pintype "input"))
    )
    (net (code "20") (name "ADDR_COUNTER_8") (class "Default")
      (node (ref "E19") (pin "7") (pinfunction "QD_7") (pintype "output"))
      (node (ref "E24") (pin "2") (pinfunction "I1_2") (pintype "input"))
      (node (ref "E27") (pin "1") (pinfunction "I0_1") (pintype "input"))
    )
    (net (code "21") (name "ADDR_COUNTER_16") (class "Default")
      (node (ref "E20") (pin "3") (pinfunction "QA_3") (pintype "output"))
      (node (ref "E28") (pin "5") (pinfunction "I1_5") (pintype "input"))
    )
    (net (code "22") (name "ADDR_COUNTER_32") (class "Default")
      (node (ref "E20") (pin "2") (pinfunction "QB_2") (pintype "output"))
      (node (ref "E23") (pin "3") (pinfunction "I0_3") (pintype "input"))
      (node (ref "E28") (pin "1") (pinfunction "I0_1") (pintype "input"))
    )
    (net (code "23") (name "ADDR_COUNTER_64") (class "Default")
      (node (ref "E20") (pin "6") (pinfunction "QC_6") (pintype "output"))
      (node (ref "E23") (pin "4") (pinfunction "I1_4") (pintype "input"))
      (node (ref "E24") (pin "4") (pinfunction "I2_4") (pintype "input"))
      (node (ref "E29") (pin "5") (pinfunction "I1_5") (pintype "input"))
    )
    (net (code "24") (name "ADDR_COUNTER_128") (class "Default")
      (node (ref "E20") (pin "7") (pinfunction "QD_7") (pintype "output"))
      (node (ref "E23") (pin "5") (pinfunction "I2_5") (pintype "input"))
      (node (ref "E24") (pin "5") (pinfunction "I3_5") (pintype "input"))
      (node (ref "E29") (pin "1") (pinfunction "I0_1") (pintype "input"))
    )
    (net (code "25") (name "ADDR_SOURCE_H") (class "Default")
      (node (ref "E18") (pin "5") (pinfunction "Q_5") (pintype "output"))
      (node (ref "E26") (pin "10") (pinfunction "I1_10") (pintype "input"))
      (node (ref "E26") (pin "13") (pinfunction "I1_13") (pintype "input"))
      (node (ref "E27") (pin "10") (pinfunction "I1_10") (pintype "input"))
      (node (ref "E27") (pin "13") (pinfunction "I1_13") (pintype "input"))
      (node (ref "E28") (pin "10") (pinfunction "I1_10") (pintype "input"))
      (node (ref "E28") (pin "13") (pinfunction "I1_13") (pintype "input"))
      (node (ref "E29") (pin "10") (pinfunction "I1_10") (pintype "input"))
      (node (ref "E29") (pin "13") (pinfunction "I1_13") (pintype "input"))
    )
    (net (code "26") (name "ADDR_SOURCE_L") (class "Default")
      (node (ref "E16") (pin "10") (pinfunction "I1_10") (pintype "input"))
      (node (ref "E16") (pin "4") (pinfunction "I1_4") (pintype "input"))
      (node (ref "E18") (pin "2") (pinfunction "D_2") (pintype "input"))
      (node (ref "E18") (pin "6") (pinfunction "~{Q}_6") (pintype "output"))
      (node (ref "E26") (pin "2") (pinfunction "I1_2") (pintype "input"))
      (node (ref "E26") (pin "4") (pinfunction "I0_4") (pintype "input"))
      (node (ref "E27") (pin "2") (pinfunction "I1_2") (pintype "input"))
      (node (ref "E27") (pin "4") (pinfunction "I0_4") (pintype "input"))
      (node (ref "E28") (pin "2") (pinfunction "I1_2") (pintype "input"))
      (node (ref "E28") (pin "4") (pinfunction "I0_4") (pintype "input"))
      (node (ref "E29") (pin "2") (pinfunction "I1_2") (pintype "input"))
      (node (ref "E29") (pin "4") (pinfunction "I0_4") (pintype "input"))
    )
    (net (code "27") (name "BIT_0L") (class "Default")
      (node (ref "BIT0") (pin "2") (pinfunction "P_2") (pintype "passive"))
      (node (ref "E1") (pin "5") (pinfunction "I2_5") (pintype "input"))
    )
    (net (code "28") (name "BIT_1L") (class "Default")
      (node (ref "BIT1") (pin "2") (pinfunction "P_2") (pintype "passive"))
      (node (ref "E1") (pin "9") (pinfunction "I0_9") (pintype "input"))
    )
    (net (code "29") (name "BIT_2L") (class "Default")
      (node (ref "BIT2") (pin "2") (pinfunction "P_2") (pintype "passive"))
      (node (ref "E1") (pin "13") (pinfunction "I2_13") (pintype "input"))
    )
    (net (code "30") (name "BIT_3L") (class "Default")
      (node (ref "BIT3") (pin "2") (pinfunction "P_2") (pintype "passive"))
      (node (ref "E4") (pin "5") (pinfunction "I3_5") (pintype "input"))
    )
    (net (code "31") (name "BUS_AC_LO_L") (class "Default")
      (node (ref "C39") (pin "1") (pinfunction "1_1") (pintype "passive"))
      (node (ref "J1") (pin "VV") (pinfunction "P$2_VV") (pintype "bidirectional"))
      (node (ref "R46") (pin "1") (pinfunction "1_1") (pintype "passive"))
    )
    (net (code "32") (name "BUS_ADDRESS_INVALID_L") (class "Default")
      (node (ref "E17") (pin "5") (pinfunction "I1_5") (pintype "input"))
      (node (ref "J2") (pin "C") (pinfunction "P$2_C") (pintype "bidirectional"))
      (node (ref "R26") (pin "1") (pinfunction "1_1") (pintype "passive"))
      (node (ref "RN3") (pin "3") (pinfunction "2_3") (pintype "passive"))
      (node (ref "RN7") (pin "3") (pinfunction "2_3") (pintype "passive"))
    )
    (net (code "33") (name "BUS_ADDR_ACCEPTED_L") (class "Default")
      (node (ref "J2") (pin "H") (pinfunction "P$2_H") (pintype "bidirectional"))
      (node (ref "RN3") (pin "5") (pinfunction "2_5") (pintype "passive"))
      (node (ref "RN7") (pin "5") (pinfunction "2_5") (pintype "passive"))
    )
    (net (code "34") (name "BUS_CA_00_L") (class "Default")
      (node (ref "E30") (pin "5") (pinfunction "O_5") (pintype "open_collector"))
      (node (ref "J2") (pin "Y") (pinfunction "P$2_Y") (pintype "bidirectional"))
      (node (ref "R147") (pin "1") (pinfunction "1_1") (pintype "passive"))
      (node (ref "R148") (pin "2") (pinfunction "2_2") (pintype "passive"))
    )
    (net (code "35") (name "BUS_CA_01_L") (class "Default")
      (node (ref "E30") (pin "3") (pinfunction "O_3") (pintype "open_collector"))
      (node (ref "J2") (pin "SS") (pinfunction "P$2_SS") (pintype "bidirectional"))
      (node (ref "RN4") (pin "3") (pinfunction "2_3") (pintype "passive"))
      (node (ref "RN8") (pin "3") (pinfunction "2_3") (pintype "passive"))
    )
    (net (code "36") (name "BUS_CA_02_L") (class "Default")
      (node (ref "E31") (pin "5") (pinfunction "O_5") (pintype "open_collector"))
      (node (ref "J2") (pin "U") (pinfunction "P$2_U") (pintype "bidirectional"))
      (node (ref "RN3") (pin "10") (pinfunction "2_10") (pintype "passive"))
      (node (ref "RN7") (pin "10") (pinfunction "2_10") (pintype "passive"))
    )
    (net (code "37") (name "BUS_CA_03_L") (class "Default")
      (node (ref "E31") (pin "3") (pinfunction "O_3") (pintype "open_collector"))
      (node (ref "J2") (pin "UU") (pinfunction "P$2_UU") (pintype "bidirectional"))
      (node (ref "RN4") (pin "2") (pinfunction "2_2") (pintype "passive"))
      (node (ref "RN8") (pin "2") (pinfunction "2_2") (pintype "passive"))
    )
    (net (code "38") (name "BUS_CA_04_L") (class "Default")
      (node (ref "E32") (pin "5") (pinfunction "O_5") (pintype "open_collector"))
      (node (ref "J2") (pin "MM") (pinfunction "P$2_MM") (pintype "bidirectional"))
      (node (ref "RN4") (pin "5") (pinfunction "2_5") (pintype "passive"))
      (node (ref "RN8") (pin "5") (pinfunction "2_5") (pintype "passive"))
    )
    (net (code "39") (name "BUS_CA_05_L") (class "Default")
      (node (ref "E32") (pin "3") (pinfunction "O_3") (pintype "open_collector"))
      (node (ref "J2") (pin "CC") (pinfunction "P$2_CC") (pintype "bidirectional"))
      (node (ref "RN4") (pin "9") (pinfunction "2_9") (pintype "passive"))
      (node (ref "RN8") (pin "9") (pinfunction "2_9") (pintype "passive"))
    )
    (net (code "40") (name "BUS_CA_06_L") (class "Default")
      (node (ref "E33") (pin "5") (pinfunction "O_5") (pintype "open_collector"))
      (node (ref "J2") (pin "PP") (pinfunction "P$2_PP") (pintype "bidirectional"))
      (node (ref "RN4") (pin "4") (pinfunction "2_4") (pintype "passive"))
      (node (ref "RN8") (pin "4") (pinfunction "2_4") (pintype "passive"))
    )
    (net (code "41") (name "BUS_CA_07_L") (class "Default")
      (node (ref "E33") (pin "3") (pinfunction "O_3") (pintype "open_collector"))
      (node (ref "J2") (pin "HH") (pinfunction "P$2_HH") (pintype "bidirectional"))
      (node (ref "RN4") (pin "7") (pinfunction "2_7") (pintype "passive"))
      (node (ref "RN8") (pin "7") (pinfunction "2_7") (pintype "passive"))
    )
    (net (code "42") (name "BUS_DATA&CLOCK_L") (class "Default")
      (node (ref "E9") (pin "10") (pinfunction "O_10") (pintype "open_collector"))
      (node (ref "J2") (pin "KK") (pinfunction "P$2_KK") (pintype "bidirectional"))
      (node (ref "RN4") (pin "6") (pinfunction "2_6") (pintype "passive"))
      (node (ref "RN8") (pin "6") (pinfunction "2_6") (pintype "passive"))
    )
    (net (code "43") (name "BUS_DC_LO_L") (class "Default")
      (node (ref "C53") (pin "1") (pinfunction "1_1") (pintype "passive"))
      (node (ref "J1") (pin "TT") (pinfunction "P$2_TT") (pintype "bidirectional"))
      (node (ref "R50") (pin "1") (pinfunction "1_1") (pintype "passive"))
    )
    (net (code "44") (name "BUS_FILE_READY") (class "Default")
      (node (ref "J1") (pin "V") (pinfunction "P$2_V") (pintype "bidirectional"))
      (node (ref "RN1") (pin "9") (pinfunction "2_9") (pintype "passive"))
      (node (ref "RN5") (pin "9") (pinfunction "2_9") (pintype "passive"))
    )
    (net (code "45") (name "BUS_HIGH_DENSITY_L") (class "Default")
      (node (ref "J1") (pin "N") (pinfunction "P$2_N") (pintype "bidirectional"))
      (node (ref "RN1") (pin "6") (pinfunction "2_6") (pintype "passive"))
      (node (ref "RN5") (pin "6") (pinfunction "2_6") (pintype "passive"))
    )
    (net (code "46") (name "BUS_INDEX_L") (class "Default")
      (node (ref "E11") (pin "1") (pinfunction "CLR_1") (pintype "input"))
      (node (ref "E11") (pin "11") (pinfunction "CLK_11") (pintype "input"))
      (node (ref "J1") (pin "Z") (pinfunction "P$2_Z") (pintype "bidirectional"))
      (node (ref "RN2") (pin "10") (pinfunction "2_10") (pintype "passive"))
      (node (ref "RN6") (pin "10") (pinfunction "2_10") (pintype "passive"))
    )
    (net (code "47") (name "BUS_READ_GATE_L") (class "Default")
      (node (ref "J1") (pin "L") (pinfunction "P$2_L") (pintype "bidirectional"))
      (node (ref "RN1") (pin "5") (pinfunction "2_5") (pintype "passive"))
      (node (ref "RN5") (pin "5") (pinfunction "2_5") (pintype "passive"))
    )
    (net (code "48") (name "BUS_RESTORE_L") (class "Default")
      (node (ref "C34") (pin "1") (pinfunction "1_1") (pintype "passive"))
      (node (ref "E22") (pin "5") (pinfunction "O_5") (pintype "open_collector"))
      (node (ref "J2") (pin "P") (pinfunction "P$2_P") (pintype "bidirectional"))
      (node (ref "RN3") (pin "8") (pinfunction "2_8") (pintype "passive"))
      (node (ref "RN7") (pin "8") (pinfunction "2_8") (pintype "passive"))
    )
    (net (code "49") (name "BUS_RWS_READY_L") (class "Default")
      (node (ref "E12") (pin "5") (pinfunction "I_5") (pintype "input"))
      (node (ref "J2") (pin "EE") (pinfunction "P$2_EE") (pintype "bidirectional"))
      (node (ref "RN4") (pin "8") (pinfunction "2_8") (pintype "passive"))
      (node (ref "RN8") (pin "8") (pinfunction "2_8") (pintype "passive"))
    )
    (net (code "50") (name "BUS_SECTOR_ADDR_0L") (class "Default")
      (node (ref "E6") (pin "5") (pinfunction "I_5") (pintype "input"))
      (node (ref "J1") (pin "DD") (pinfunction "P$2_DD") (pintype "bidirectional"))
      (node (ref "R17") (pin "1") (pinfunction "1_1") (pintype "passive"))
      (node (ref "RN2") (pin "8") (pinfunction "2_8") (pintype "passive"))
      (node (ref "RN6") (pin "8") (pinfunction "2_8") (pintype "passive"))
    )
    (net (code "51") (name "BUS_SECTOR_ADDR_1L") (class "Default")
      (node (ref "E6") (pin "13") (pinfunction "I_13") (pintype "input"))
      (node (ref "J2") (pin "K") (pinfunction "P$2_K") (pintype "bidirectional"))
      (node (ref "R18") (pin "1") (pinfunction "1_1") (pintype "passive"))
      (node (ref "RN3") (pin "6") (pinfunction "2_6") (pintype "passive"))
      (node (ref "RN7") (pin "6") (pinfunction "2_6") (pintype "passive"))
    )
    (net (code "52") (name "BUS_SECTOR_ADDR_2L") (class "Default")
      (node (ref "E6") (pin "11") (pinfunction "I_11") (pintype "input"))
      (node (ref "J1") (pin "FF") (pinfunction "P$2_FF") (pintype "bidirectional"))
      (node (ref "R16") (pin "1") (pinfunction "1_1") (pintype "passive"))
      (node (ref "RN2") (pin "7") (pinfunction "2_7") (pintype "passive"))
      (node (ref "RN6") (pin "7") (pinfunction "2_7") (pintype "passive"))
    )
    (net (code "53") (name "BUS_SECTOR_ADDR_3L") (class "Default")
      (node (ref "E6") (pin "9") (pinfunction "I_9") (pintype "input"))
      (node (ref "J1") (pin "LL") (pinfunction "P$2_LL") (pintype "bidirectional"))
      (node (ref "R11") (pin "1") (pinfunction "1_1") (pintype "passive"))
      (node (ref "RN2") (pin "5") (pinfunction "2_5") (pintype "passive"))
      (node (ref "RN6") (pin "5") (pinfunction "2_5") (pintype "passive"))
    )
    (net (code "54") (name "BUS_SECTOR_PULSE_L") (class "Default")
      (node (ref "J1") (pin "T") (pinfunction "P$2_T") (pintype "bidirectional"))
      (node (ref "RN1") (pin "8") (pinfunction "2_8") (pintype "passive"))
      (node (ref "RN5") (pin "8") (pinfunction "2_8") (pintype "passive"))
    )
    (net (code "55") (name "BUS_SEEK_INCOMPLETE_L") (class "Default")
      (node (ref "E21") (pin "7") (pinfunction "I1_7") (pintype "input"))
      (node (ref "J2") (pin "E") (pinfunction "P$2_E") (pintype "bidirectional"))
      (node (ref "R27") (pin "1") (pinfunction "1_1") (pintype "passive"))
      (node (ref "RN3") (pin "4") (pinfunction "2_4") (pintype "passive"))
      (node (ref "RN7") (pin "4") (pinfunction "2_4") (pintype "passive"))
    )
    (net (code "56") (name "BUS_STROBE_L") (class "Default")
      (node (ref "E22") (pin "3") (pinfunction "O_3") (pintype "open_collector"))
      (node (ref "J1") (pin "RR") (pinfunction "P$2_RR") (pintype "bidirectional"))
      (node (ref "RN2") (pin "3") (pinfunction "2_3") (pintype "passive"))
      (node (ref "RN6") (pin "3") (pinfunction "2_3") (pintype "passive"))
    )
    (net (code "57") (name "BUS_WP_SET_L") (class "Default")
      (node (ref "J1") (pin "J") (pinfunction "P$2_J") (pintype "bidirectional"))
      (node (ref "RN1") (pin "4") (pinfunction "2_4") (pintype "passive"))
      (node (ref "RN5") (pin "4") (pinfunction "2_4") (pintype "passive"))
    )
    (net (code "58") (name "BUS_WP_STATUS_L") (class "Default")
      (node (ref "J1") (pin "R") (pinfunction "P$2_R") (pintype "bidirectional"))
      (node (ref "RN1") (pin "7") (pinfunction "2_7") (pintype "passive"))
      (node (ref "RN5") (pin "7") (pinfunction "2_7") (pintype "passive"))
    )
    (net (code "59") (name "BUS_WRITE_CK") (class "Default")
      (node (ref "J1") (pin "JJ") (pinfunction "P$2_JJ") (pintype "bidirectional"))
      (node (ref "RN2") (pin "6") (pinfunction "2_6") (pintype "passive"))
      (node (ref "RN6") (pin "6") (pinfunction "2_6") (pintype "passive"))
    )
    (net (code "60") (name "BUS_WRITE_GATE_L") (class "Default")
      (node (ref "E9") (pin "13") (pinfunction "O_13") (pintype "open_collector"))
      (node (ref "J1") (pin "BB") (pinfunction "P$2_BB") (pintype "bidirectional"))
      (node (ref "RN2") (pin "9") (pinfunction "2_9") (pintype "passive"))
      (node (ref "RN6") (pin "9") (pinfunction "2_9") (pintype "passive"))
    )
    (net (code "61") (name "CA_SW_1") (class "Default")
      (node (ref "CYL1") (pin "3") (pinfunction "S_3") (pintype "passive"))
      (node (ref "E26") (pin "9") (pinfunction "I0_9") (pintype "input"))
      (node (ref "R45") (pin "2") (pinfunction "2_2") (pintype "passive"))
    )
    (net (code "62") (name "CA_SW_2") (class "Default")
      (node (ref "CYL2") (pin "3") (pinfunction "S_3") (pintype "passive"))
      (node (ref "E26") (pin "12") (pinfunction "I0_12") (pintype "input"))
      (node (ref "R44") (pin "2") (pinfunction "2_2") (pintype "passive"))
    )
    (net (code "63") (name "CA_SW_4") (class "Default")
      (node (ref "CYL4") (pin "3") (pinfunction "S_3") (pintype "passive"))
      (node (ref "E27") (pin "9") (pinfunction "I0_9") (pintype "input"))
      (node (ref "R43") (pin "2") (pinfunction "2_2") (pintype "passive"))
    )
    (net (code "64") (name "CA_SW_8") (class "Default")
      (node (ref "CYL8") (pin "3") (pinfunction "S_3") (pintype "passive"))
      (node (ref "E27") (pin "12") (pinfunction "I0_12") (pintype "input"))
      (node (ref "R42") (pin "2") (pinfunction "2_2") (pintype "passive"))
    )
    (net (code "65") (name "CA_SW_16") (class "Default")
      (node (ref "CYL16") (pin "3") (pinfunction "S_3") (pintype "passive"))
      (node (ref "E28") (pin "9") (pinfunction "I0_9") (pintype "input"))
      (node (ref "R41") (pin "2") (pinfunction "2_2") (pintype "passive"))
    )
    (net (code "66") (name "CA_SW_32") (class "Default")
      (node (ref "CYL32") (pin "3") (pinfunction "S_3") (pintype "passive"))
      (node (ref "E28") (pin "12") (pinfunction "I0_12") (pintype "input"))
      (node (ref "R40") (pin "2") (pinfunction "2_2") (pintype "passive"))
    )
    (net (code "67") (name "CA_SW_64") (class "Default")
      (node (ref "CYL64") (pin "3") (pinfunction "S_3") (pintype "passive"))
      (node (ref "E29") (pin "9") (pinfunction "I0_9") (pintype "input"))
      (node (ref "R39") (pin "2") (pinfunction "2_2") (pintype "passive"))
    )
    (net (code "68") (name "CA_SW_128") (class "Default")
      (node (ref "CYL128") (pin "3") (pinfunction "S_3") (pintype "passive"))
      (node (ref "E29") (pin "12") (pinfunction "I0_12") (pintype "input"))
      (node (ref "R38") (pin "2") (pinfunction "2_2") (pintype "passive"))
    )
    (net (code "69") (name "CLOCK_H") (class "Default")
      (node (ref "E7") (pin "10") (pinfunction "I1_10") (pintype "input"))
      (node (ref "E7") (pin "12") (pinfunction "I0_12") (pintype "input"))
      (node (ref "E8") (pin "1") (pinfunction "A_1") (pintype "input"))
      (node (ref "E8") (pin "5") (pinfunction "Q_5") (pintype "output"))
    )
    (net (code "70") (name "CONSTANT_WRITE_L") (class "Default")
      (node (ref "CW") (pin "2") (pinfunction "P_2") (pintype "passive"))
      (node (ref "E11") (pin "4") (pinfunction "PRE_4") (pintype "input"))
    )
    (net (code "71") (name "DC_ERASE") (class "Default")
      (node (ref "DC_ERASE") (pin "2") (pinfunction "P_2") (pintype "passive"))
      (node (ref "E9") (pin "8") (pinfunction "I0_8") (pintype "input"))
    )
    (net (code "72") (name "FWD_L") (class "Default")
      (node (ref "E16") (pin "9") (pinfunction "I0_9") (pintype "input"))
      (node (ref "E17") (pin "9") (pinfunction "I0_9") (pintype "input"))
      (node (ref "FWD/REV") (pin "3") (pinfunction "S_3") (pintype "passive"))
      (node (ref "R36") (pin "1") (pinfunction "1_1") (pintype "passive"))
    )
    (net (code "73") (name "GND") (class "Default")
      (node (ref "BIT0") (pin "1") (pinfunction "O_1") (pintype "passive"))
      (node (ref "BIT1") (pin "1") (pinfunction "O_1") (pintype "passive"))
      (node (ref "BIT2") (pin "1") (pinfunction "O_1") (pintype "passive"))
      (node (ref "BIT3") (pin "1") (pinfunction "O_1") (pintype "passive"))
      (node (ref "C1") (pin "2") (pinfunction "2_2") (pintype "passive"))
      (node (ref "C10") (pin "2") (pinfunction "2_2") (pintype "passive"))
      (node (ref "C11") (pin "2") (pinfunction "2_2") (pintype "passive"))
      (node (ref "C12") (pin "2") (pinfunction "2_2") (pintype "passive"))
      (node (ref "C13") (pin "2") (pinfunction "2_2") (pintype "passive"))
      (node (ref "C14") (pin "2") (pinfunction "2_2") (pintype "passive"))
      (node (ref "C15") (pin "2") (pinfunction "2_2") (pintype "passive"))
      (node (ref "C16") (pin "2") (pinfunction "2_2") (pintype "passive"))
      (node (ref "C17") (pin "2") (pinfunction "2_2") (pintype "passive"))
      (node (ref "C18") (pin "2") (pinfunction "2_2") (pintype "passive"))
      (node (ref "C19") (pin "2") (pinfunction "2_2") (pintype "passive"))
      (node (ref "C2") (pin "2") (pinfunction "2_2") (pintype "passive"))
      (node (ref "C20") (pin "2") (pinfunction "2_2") (pintype "passive"))
      (node (ref "C21") (pin "2") (pinfunction "2_2") (pintype "passive"))
      (node (ref "C22") (pin "2") (pinfunction "2_2") (pintype "passive"))
      (node (ref "C23") (pin "2") (pinfunction "2_2") (pintype "passive"))
      (node (ref "C24") (pin "2") (pinfunction "2_2") (pintype "passive"))
      (node (ref "C26") (pin "2") (pinfunction "2_2") (pintype "passive"))
      (node (ref "C27") (pin "2") (pinfunction "2_2") (pintype "passive"))
      (node (ref "C28") (pin "2") (pinfunction "2_2") (pintype "passive"))
      (node (ref "C29") (pin "2") (pinfunction "2_2") (pintype "passive"))
      (node (ref "C3") (pin "2") (pinfunction "2_2") (pintype "passive"))
      (node (ref "C30") (pin "2") (pinfunction "2_2") (pintype "passive"))
      (node (ref "C31") (pin "2") (pinfunction "2_2") (pintype "passive"))
      (node (ref "C32") (pin "2") (pinfunction "2_2") (pintype "passive"))
      (node (ref "C33") (pin "2") (pinfunction "2_2") (pintype "passive"))
      (node (ref "C34") (pin "2") (pinfunction "2_2") (pintype "passive"))
      (node (ref "C36") (pin "2") (pinfunction "2_2") (pintype "passive"))
      (node (ref "C38") (pin "2") (pinfunction "2_2") (pintype "passive"))
      (node (ref "C39") (pin "2") (pinfunction "2_2") (pintype "passive"))
      (node (ref "C4") (pin "2") (pinfunction "2_2") (pintype "passive"))
      (node (ref "C40") (pin "2") (pinfunction "2_2") (pintype "passive"))
      (node (ref "C41") (pin "2") (pinfunction "2_2") (pintype "passive"))
      (node (ref "C42") (pin "2") (pinfunction "2_2") (pintype "passive"))
      (node (ref "C43") (pin "2") (pinfunction "2_2") (pintype "passive"))
      (node (ref "C44") (pin "-") (pinfunction "-_-") (pintype "passive"))
      (node (ref "C45") (pin "+") (pinfunction "+_+") (pintype "passive"))
      (node (ref "C5") (pin "2") (pinfunction "2_2") (pintype "passive"))
      (node (ref "C52") (pin "-") (pinfunction "-_-") (pintype "passive"))
      (node (ref "C53") (pin "2") (pinfunction "2_2") (pintype "passive"))
      (node (ref "C6") (pin "2") (pinfunction "2_2") (pintype "passive"))
      (node (ref "C60") (pin "-") (pinfunction "-_-") (pintype "passive"))
      (node (ref "C61") (pin "-") (pinfunction "-_-") (pintype "passive"))
      (node (ref "C67") (pin "-") (pinfunction "-_-") (pintype "passive"))
      (node (ref "C68") (pin "-") (pinfunction "-_-") (pintype "passive"))
      (node (ref "C7") (pin "2") (pinfunction "2_2") (pintype "passive"))
      (node (ref "C8") (pin "2") (pinfunction "2_2") (pintype "passive"))
      (node (ref "C9") (pin "2") (pinfunction "2_2") (pintype "passive"))
      (node (ref "CW") (pin "3") (pinfunction "S_3") (pintype "passive"))
      (node (ref "CYL1") (pin "2") (pinfunction "P_2") (pintype "passive"))
      (node (ref "CYL128") (pin "2") (pinfunction "P_2") (pintype "passive"))
      (node (ref "CYL16") (pin "2") (pinfunction "P_2") (pintype "passive"))
      (node (ref "CYL2") (pin "2") (pinfunction "P_2") (pintype "passive"))
      (node (ref "CYL32") (pin "2") (pinfunction "P_2") (pintype "passive"))
      (node (ref "CYL4") (pin "2") (pinfunction "P_2") (pintype "passive"))
      (node (ref "CYL64") (pin "2") (pinfunction "P_2") (pintype "passive"))
      (node (ref "CYL8") (pin "2") (pinfunction "P_2") (pintype "passive"))
      (node (ref "D5") (pin "A") (pinfunction "A_A") (pintype "passive"))
      (node (ref "DC_ERASE") (pin "3") (pinfunction "S_3") (pintype "passive"))
      (node (ref "DRIVE") (pin "A") (pinfunction "A_A") (pintype "passive"))
      (node (ref "E12") (pin "9") (pinfunction "I_9") (pintype "input"))
      (node (ref "E14") (pin "1") (pinfunction "A_1") (pintype "input"))
      (node (ref "E14") (pin "9") (pinfunction "A_9") (pintype "input"))
      (node (ref "E15") (pin "10") (pinfunction "I1_10") (pintype "input"))
      (node (ref "E15") (pin "12") (pinfunction "I0_12") (pintype "input"))
      (node (ref "E15") (pin "13") (pinfunction "I1_13") (pintype "input"))
      (node (ref "E15") (pin "4") (pinfunction "I0_4") (pintype "input"))
      (node (ref "E15") (pin "5") (pinfunction "I1_5") (pintype "input"))
      (node (ref "E15") (pin "9") (pinfunction "I0_9") (pintype "input"))
      (node (ref "E19") (pin "10") (pinfunction "C_10") (pintype "input"))
      (node (ref "E19") (pin "15") (pinfunction "A_15") (pintype "input"))
      (node (ref "E20") (pin "1") (pinfunction "B_1") (pintype "input"))
      (node (ref "E20") (pin "15") (pinfunction "A_15") (pintype "input"))
      (node (ref "E24") (pin "10") (pinfunction "I1_10") (pintype "input"))
      (node (ref "E24") (pin "12") (pinfunction "I2_12") (pintype "input"))
      (node (ref "E24") (pin "13") (pinfunction "I3_13") (pintype "input"))
      (node (ref "E24") (pin "9") (pinfunction "I0_9") (pintype "input"))
      (node (ref "E5") (pin "2") (pinfunction "D_2") (pintype "input"))
      (node (ref "E5") (pin "3") (pinfunction "CLK_3") (pintype "input"))
      (node (ref "E6") (pin "1") (pinfunction "I_1") (pintype "input"))
      (node (ref "E8") (pin "9") (pinfunction "A_9") (pintype "input"))
      (node (ref "E9") (pin "2") (pinfunction "I0_2") (pintype "input"))
      (node (ref "E9") (pin "3") (pinfunction "I1_3") (pintype "input"))
      (node (ref "E9") (pin "5") (pinfunction "I0_5") (pintype "input"))
      (node (ref "E9") (pin "6") (pinfunction "I1_6") (pintype "input"))
      (node (ref "FUNCTION") (pin "A") (pinfunction "A_A") (pintype "passive"))
      (node (ref "FWD/REV") (pin "2") (pinfunction "P_2") (pintype "passive"))
      (node (ref "HEAD") (pin "3") (pinfunction "S_3") (pintype "passive"))
      (node (ref "J1") (pin "A") (pinfunction "P$2_A") (pintype "bidirectional"))
      (node (ref "J1") (pin "AA") (pinfunction "P$2_AA") (pintype "bidirectional"))
      (node (ref "J1") (pin "B") (pinfunction "P$2_B") (pintype "bidirectional"))
      (node (ref "J1") (pin "C") (pinfunction "P$2_C") (pintype "bidirectional"))
      (node (ref "J1") (pin "CC") (pinfunction "P$2_CC") (pintype "bidirectional"))
      (node (ref "J1") (pin "E") (pinfunction "P$2_E") (pintype "bidirectional"))
      (node (ref "J1") (pin "EE") (pinfunction "P$2_EE") (pintype "bidirectional"))
      (node (ref "J1") (pin "H") (pinfunction "P$2_H") (pintype "bidirectional"))
      (node (ref "J1") (pin "HH") (pinfunction "P$2_HH") (pintype "bidirectional"))
      (node (ref "J1") (pin "K") (pinfunction "P$2_K") (pintype "bidirectional"))
      (node (ref "J1") (pin "KK") (pinfunction "P$2_KK") (pintype "bidirectional"))
      (node (ref "J1") (pin "M") (pinfunction "P$2_M") (pintype "bidirectional"))
      (node (ref "J1") (pin "MM") (pinfunction "P$2_MM") (pintype "bidirectional"))
      (node (ref "J1") (pin "P") (pinfunction "P$2_P") (pintype "bidirectional"))
      (node (ref "J1") (pin "PP") (pinfunction "P$2_PP") (pintype "bidirectional"))
      (node (ref "J1") (pin "S") (pinfunction "P$2_S") (pintype "bidirectional"))
      (node (ref "J1") (pin "SS") (pinfunction "P$2_SS") (pintype "bidirectional"))
      (node (ref "J1") (pin "U") (pinfunction "P$2_U") (pintype "bidirectional"))
      (node (ref "J1") (pin "UU") (pinfunction "P$2_UU") (pintype "bidirectional"))
      (node (ref "J1") (pin "W") (pinfunction "P$2_W") (pintype "bidirectional"))
      (node (ref "J1") (pin "Y") (pinfunction "P$2_Y") (pintype "bidirectional"))
      (node (ref "J2") (pin "B") (pinfunction "P$2_B") (pintype "bidirectional"))
      (node (ref "J2") (pin "BB") (pinfunction "P$2_BB") (pintype "bidirectional"))
      (node (ref "J2") (pin "D") (pinfunction "P$2_D") (pintype "bidirectional"))
      (node (ref "J2") (pin "DD") (pinfunction "P$2_DD") (pintype "bidirectional"))
      (node (ref "J2") (pin "F") (pinfunction "P$2_F") (pintype "bidirectional"))
      (node (ref "J2") (pin "FF") (pinfunction "P$2_FF") (pintype "bidirectional"))
      (node (ref "J2") (pin "J") (pinfunction "P$2_J") (pintype "bidirectional"))
      (node (ref "J2") (pin "JJ") (pinfunction "P$2_JJ") (pintype "bidirectional"))
      (node (ref "J2") (pin "L") (pinfunction "P$2_L") (pintype "bidirectional"))
      (node (ref "J2") (pin "LL") (pinfunction "P$2_LL") (pintype "bidirectional"))
      (node (ref "J2") (pin "N") (pinfunction "P$2_N") (pintype "bidirectional"))
      (node (ref "J2") (pin "NN") (pinfunction "P$2_NN") (pintype "bidirectional"))
      (node (ref "J2") (pin "R") (pinfunction "P$2_R") (pintype "bidirectional"))
      (node (ref "J2") (pin "RR") (pinfunction "P$2_RR") (pintype "bidirectional"))
      (node (ref "J2") (pin "T") (pinfunction "P$2_T") (pintype "bidirectional"))
      (node (ref "J2") (pin "TT") (pinfunction "P$2_TT") (pintype "bidirectional"))
      (node (ref "J2") (pin "V") (pinfunction "P$2_V") (pintype "bidirectional"))
      (node (ref "J2") (pin "VV") (pinfunction "P$2_VV") (pintype "bidirectional"))
      (node (ref "J2") (pin "X") (pinfunction "P$2_X") (pintype "bidirectional"))
      (node (ref "J2") (pin "Z") (pinfunction "P$2_Z") (pintype "bidirectional"))
      (node (ref "POWER") (pin "1") (pinfunction "1_1") (pintype "passive"))
      (node (ref "POWER_ON") (pin "B") (pinfunction "B_B") (pintype "passive"))
      (node (ref "R14") (pin "1") (pinfunction "1_1") (pintype "passive"))
      (node (ref "R148") (pin "1") (pinfunction "1_1") (pintype "passive"))
      (node (ref "R15") (pin "1") (pinfunction "1_1") (pintype "passive"))
      (node (ref "R23") (pin "1") (pinfunction "1_1") (pintype "passive"))
      (node (ref "R31") (pin "1") (pinfunction "1_1") (pintype "passive"))
      (node (ref "R70") (pin "1") (pinfunction "1_1") (pintype "passive"))
      (node (ref "RN5") (pin "1") (pinfunction "1_1") (pintype "passive"))
      (node (ref "RN6") (pin "1") (pinfunction "1_1") (pintype "passive"))
      (node (ref "RN6") (pin "2") (pinfunction "2_2") (pintype "passive"))
      (node (ref "RN7") (pin "1") (pinfunction "1_1") (pintype "passive"))
      (node (ref "RN8") (pin "1") (pinfunction "1_1") (pintype "passive"))
      (node (ref "RTZ") (pin "2") (pinfunction "P_2") (pintype "passive"))
      (node (ref "SECTOR") (pin "11") (pinfunction "11_11") (pintype "passive"))
      (node (ref "SECTOR") (pin "12") (pinfunction "12_12") (pintype "passive"))
      (node (ref "WRITE") (pin "2") (pinfunction "P_2") (pintype "passive"))
    )
    (net (code "74") (name "HEAD_SELECT_L") (class "Default")
      (node (ref "HEAD") (pin "2") (pinfunction "P_2") (pintype "passive"))
      (node (ref "J1") (pin "X") (pinfunction "P$2_X") (pintype "bidirectional"))
      (node (ref "RN1") (pin "10") (pinfunction "2_10") (pintype "passive"))
      (node (ref "RN5") (pin "10") (pinfunction "2_10") (pintype "passive"))
    )
    (net (code "75") (name "NEG1_DETECT_L") (class "Default")
      (node (ref "E23") (pin "10") (pinfunction "I1_10") (pintype "input"))
      (node (ref "E23") (pin "6") (pinfunction "O_6") (pintype "output"))
    )
    (net (code "76") (name "Net-(ADDR_INV-PadA)") (class "Default")
      (node (ref "ADDR_INV") (pin "A") (pinfunction "A_A") (pintype "passive"))
      (node (ref "R1") (pin "1") (pinfunction "1_1") (pintype "passive"))
    )
    (net (code "77") (name "Net-(BIT0-S)") (class "Default")
      (node (ref "BIT0") (pin "3") (pinfunction "S_3") (pintype "passive"))
      (node (ref "BIT1") (pin "3") (pinfunction "S_3") (pintype "passive"))
      (node (ref "BIT2") (pin "3") (pinfunction "S_3") (pintype "passive"))
      (node (ref "BIT3") (pin "3") (pinfunction "S_3") (pintype "passive"))
      (node (ref "R7") (pin "1") (pinfunction "1_1") (pintype "passive"))
    )
    (net (code "78") (name "Net-(CW-O)") (class "Default")
      (node (ref "CW") (pin "1") (pinfunction "O_1") (pintype "passive"))
      (node (ref "E11") (pin "10") (pinfunction "PRE_10") (pintype "input"))
      (node (ref "E11") (pin "2") (pinfunction "D_2") (pintype "input"))
      (node (ref "R4") (pin "1") (pinfunction "1_1") (pintype "passive"))
    )
    (net (code "79") (name "Net-(D2-PadC)") (class "Default")
      (node (ref "D2") (pin "C") (pinfunction "C_C") (pintype "passive"))
      (node (ref "D3") (pin "A") (pinfunction "A_A") (pintype "passive"))
    )
    (net (code "80") (name "Net-(D3-PadC)") (class "Default")
      (node (ref "D3") (pin "C") (pinfunction "C_C") (pintype "passive"))
      (node (ref "D4") (pin "A") (pinfunction "A_A") (pintype "passive"))
    )
    (net (code "81") (name "Net-(E2A-PRE)") (class "Default")
      (node (ref "E2") (pin "10") (pinfunction "PRE_10") (pintype "input"))
      (node (ref "E2") (pin "4") (pinfunction "PRE_4") (pintype "input"))
      (node (ref "E5") (pin "10") (pinfunction "PRE_10") (pintype "input"))
      (node (ref "R10") (pin "1") (pinfunction "1_1") (pintype "passive"))
    )
    (net (code "82") (name "Net-(E3A-A)") (class "Default")
      (node (ref "E3") (pin "15") (pinfunction "A_15") (pintype "input"))
      (node (ref "E6") (pin "6") (pinfunction "O_6") (pintype "output"))
    )
    (net (code "83") (name "Net-(E3A-B)") (class "Default")
      (node (ref "E3") (pin "14") (pinfunction "B_14") (pintype "input"))
      (node (ref "E6") (pin "12") (pinfunction "O_12") (pintype "output"))
    )
    (net (code "84") (name "Net-(E3A-C)") (class "Default")
      (node (ref "E3") (pin "13") (pinfunction "C_13") (pintype "input"))
      (node (ref "E6") (pin "10") (pinfunction "O_10") (pintype "output"))
    )
    (net (code "85") (name "Net-(E3A-D)") (class "Default")
      (node (ref "E3") (pin "12") (pinfunction "D_12") (pintype "input"))
      (node (ref "E6") (pin "8") (pinfunction "O_8") (pintype "output"))
    )
    (net (code "86") (name "Net-(E4B-O)") (class "Default")
      (node (ref "E4") (pin "8") (pinfunction "O_8") (pintype "output"))
      (node (ref "E7") (pin "9") (pinfunction "I0_9") (pintype "input"))
    )
    (net (code "87") (name "Net-(E5B-CLK)") (class "Default")
      (node (ref "E5") (pin "11") (pinfunction "CLK_11") (pintype "input"))
      (node (ref "E8") (pin "12") (pinfunction "~{Q}_12") (pintype "output"))
    )
    (net (code "88") (name "Net-(E6A-O)") (class "Default")
      (node (ref "E6") (pin "2") (pinfunction "O_2") (pintype "output"))
      (node (ref "E6") (pin "3") (pinfunction "I_3") (pintype "input"))
    )
    (net (code "89") (name "Net-(E7A-O)") (class "Default")
      (node (ref "E7") (pin "3") (pinfunction "O_3") (pintype "output"))
      (node (ref "E9") (pin "12") (pinfunction "I1_12") (pintype "input"))
    )
    (net (code "90") (name "Net-(E7B-I0)") (class "Default")
      (node (ref "E7") (pin "11") (pinfunction "O_11") (pintype "output"))
      (node (ref "E7") (pin "4") (pinfunction "I0_4") (pintype "input"))
    )
    (net (code "91") (name "Net-(E7B-I1)") (class "Default")
      (node (ref "E7") (pin "5") (pinfunction "I1_5") (pintype "input"))
      (node (ref "E7") (pin "8") (pinfunction "O_8") (pintype "output"))
    )
    (net (code "92") (name "Net-(E7B-O)") (class "Default")
      (node (ref "E7") (pin "6") (pinfunction "O_6") (pintype "output"))
      (node (ref "E9") (pin "9") (pinfunction "I1_9") (pintype "input"))
    )
    (net (code "93") (name "Net-(E8A-C)") (class "Default")
      (node (ref "C63") (pin "2") (pinfunction "2_2") (pintype "passive"))
      (node (ref "E8") (pin "14") (pinfunction "C_14") (pintype "input"))
    )
    (net (code "94") (name "Net-(E8A-R{slash}C)") (class "Default")
      (node (ref "C63") (pin "1") (pinfunction "1_1") (pintype "passive"))
      (node (ref "E8") (pin "15") (pinfunction "R/C_15") (pintype "input"))
      (node (ref "R9") (pin "E") (pinfunction "E_E") (pintype "passive"))
      (node (ref "R9") (pin "S") (pinfunction "S_S") (pintype "passive"))
    )
    (net (code "95") (name "Net-(E8A-~{Q})") (class "Default")
      (node (ref "E8") (pin "10") (pinfunction "B_10") (pintype "input"))
      (node (ref "E8") (pin "4") (pinfunction "~{Q}_4") (pintype "output"))
    )
    (net (code "96") (name "Net-(E8B-C)") (class "Default")
      (node (ref "C62") (pin "2") (pinfunction "2_2") (pintype "passive"))
      (node (ref "E8") (pin "6") (pinfunction "C_6") (pintype "input"))
    )
    (net (code "97") (name "Net-(E8B-R{slash}C)") (class "Default")
      (node (ref "C62") (pin "1") (pinfunction "1_1") (pintype "passive"))
      (node (ref "E8") (pin "7") (pinfunction "R/C_7") (pintype "input"))
      (node (ref "R8") (pin "1") (pinfunction "1_1") (pintype "passive"))
    )
    (net (code "98") (name "Net-(E10A-I0)") (class "Default")
      (node (ref "E10") (pin "1") (pinfunction "I0_1") (pintype "input"))
      (node (ref "E10") (pin "2") (pinfunction "I1_2") (pintype "input"))
      (node (ref "E10") (pin "4") (pinfunction "I0_4") (pintype "input"))
      (node (ref "E10") (pin "5") (pinfunction "I1_5") (pintype "input"))
      (node (ref "E6") (pin "4") (pinfunction "O_4") (pintype "output"))
    )
    (net (code "99") (name "Net-(E10C-I1)") (class "Default")
      (node (ref "E10") (pin "10") (pinfunction "I1_10") (pintype "input"))
      (node (ref "E10") (pin "11") (pinfunction "O_11") (pintype "output"))
    )
    (net (code "100") (name "Net-(E10C-O)") (class "Default")
      (node (ref "E10") (pin "13") (pinfunction "I1_13") (pintype "input"))
      (node (ref "E10") (pin "8") (pinfunction "O_8") (pintype "output"))
      (node (ref "E11") (pin "12") (pinfunction "D_12") (pintype "input"))
      (node (ref "E11") (pin "13") (pinfunction "CLR_13") (pintype "input"))
    )
    (net (code "101") (name "Net-(E11A-CLK)") (class "Default")
      (node (ref "E11") (pin "3") (pinfunction "CLK_3") (pintype "input"))
      (node (ref "E11") (pin "9") (pinfunction "Q_9") (pintype "output"))
    )
    (net (code "102") (name "Net-(E12A-I)") (class "Default")
      (node (ref "D5") (pin "C") (pinfunction "C_C") (pintype "passive"))
      (node (ref "E12") (pin "1") (pinfunction "I_1") (pintype "input"))
      (node (ref "E13") (pin "5") (pinfunction "O_5") (pintype "open_collector"))
      (node (ref "R32") (pin "2") (pinfunction "2_2") (pintype "passive"))
    )
    (net (code "103") (name "Net-(E12A-O)") (class "Default")
      (node (ref "E12") (pin "2") (pinfunction "O_2") (pintype "output"))
      (node (ref "E15") (pin "2") (pinfunction "I1_2") (pintype "input"))
      (node (ref "E23") (pin "2") (pinfunction "I1_2") (pintype "input"))
    )
    (net (code "104") (name "Net-(E12B-O)") (class "Default")
      (node (ref "E12") (pin "4") (pinfunction "O_4") (pintype "output"))
      (node (ref "E13") (pin "6") (pinfunction "I0_6") (pintype "input"))
    )
    (net (code "105") (name "Net-(E12C-O)") (class "Default")
      (node (ref "E12") (pin "6") (pinfunction "O_6") (pintype "output"))
      (node (ref "E13") (pin "1") (pinfunction "I0_1") (pintype "input"))
    )
    (net (code "106") (name "Net-(E12D-O)") (class "Default")
      (node (ref "E12") (pin "8") (pinfunction "O_8") (pintype "output"))
      (node (ref "E18") (pin "10") (pinfunction "PRE_10") (pintype "input"))
      (node (ref "E18") (pin "11") (pinfunction "CLK_11") (pintype "input"))
      (node (ref "E18") (pin "12") (pinfunction "D_12") (pintype "input"))
      (node (ref "E18") (pin "13") (pinfunction "CLR_13") (pintype "input"))
    )
    (net (code "107") (name "Net-(E12E-I)") (class "Default")
      (node (ref "E12") (pin "11") (pinfunction "I_11") (pintype "input"))
      (node (ref "E23") (pin "12") (pinfunction "O_12") (pintype "output"))
      (node (ref "E23") (pin "9") (pinfunction "I0_9") (pintype "input"))
    )
    (net (code "108") (name "Net-(E12E-O)") (class "Default")
      (node (ref "E12") (pin "10") (pinfunction "O_10") (pintype "output"))
      (node (ref "E17") (pin "10") (pinfunction "I1_10") (pintype "input"))
      (node (ref "E17") (pin "12") (pinfunction "I0_12") (pintype "input"))
    )
    (net (code "109") (name "Net-(E12F-I)") (class "Default")
      (node (ref "C37") (pin "2") (pinfunction "2_2") (pintype "passive"))
      (node (ref "E12") (pin "13") (pinfunction "I_13") (pintype "input"))
      (node (ref "R22") (pin "1") (pinfunction "1_1") (pintype "passive"))
      (node (ref "R23") (pin "2") (pinfunction "2_2") (pintype "passive"))
    )
    (net (code "110") (name "Net-(E12F-O)") (class "Default")
      (node (ref "C37") (pin "1") (pinfunction "1_1") (pintype "passive"))
      (node (ref "E12") (pin "12") (pinfunction "O_12") (pintype "output"))
      (node (ref "E14") (pin "10") (pinfunction "B_10") (pintype "input"))
      (node (ref "E14") (pin "2") (pinfunction "B_2") (pintype "input"))
      (node (ref "E22") (pin "1") (pinfunction "I0_1") (pintype "input"))
    )
    (net (code "111") (name "Net-(E13A-O)") (class "Default")
      (node (ref "C36") (pin "1") (pinfunction "1_1") (pintype "passive"))
      (node (ref "E13") (pin "3") (pinfunction "O_3") (pintype "open_collector"))
      (node (ref "Q1") (pin "E") (pinfunction "E_E") (pintype "passive"))
      (node (ref "R20") (pin "1") (pinfunction "1_1") (pintype "passive"))
    )
    (net (code "112") (name "Net-(E13B-I1)") (class "Default")
      (node (ref "E13") (pin "7") (pinfunction "I1_7") (pintype "input"))
      (node (ref "E14") (pin "12") (pinfunction "~{Q}_12") (pintype "output"))
      (node (ref "E18") (pin "3") (pinfunction "CLK_3") (pintype "input"))
      (node (ref "E23") (pin "1") (pinfunction "I0_1") (pintype "input"))
    )
    (net (code "113") (name "Net-(E14A-C)") (class "Default")
      (node (ref "C35") (pin "2") (pinfunction "2_2") (pintype "passive"))
      (node (ref "E14") (pin "14") (pinfunction "C_14") (pintype "input"))
    )
    (net (code "114") (name "Net-(E14A-R{slash}C)") (class "Default")
      (node (ref "C35") (pin "1") (pinfunction "1_1") (pintype "passive"))
      (node (ref "E14") (pin "15") (pinfunction "R/C_15") (pintype "input"))
      (node (ref "R25") (pin "1") (pinfunction "1_1") (pintype "passive"))
    )
    (net (code "115") (name "Net-(E14A-~{Q})") (class "Default")
      (node (ref "E14") (pin "4") (pinfunction "~{Q}_4") (pintype "output"))
      (node (ref "E15") (pin "1") (pinfunction "I0_1") (pintype "input"))
    )
    (net (code "116") (name "Net-(E14B-C)") (class "Default")
      (node (ref "C25") (pin "2") (pinfunction "2_2") (pintype "passive"))
      (node (ref "E14") (pin "6") (pinfunction "C_6") (pintype "input"))
    )
    (net (code "117") (name "Net-(E14B-R{slash}C)") (class "Default")
      (node (ref "C25") (pin "1") (pinfunction "1_1") (pintype "passive"))
      (node (ref "E14") (pin "7") (pinfunction "R/C_7") (pintype "input"))
      (node (ref "R28") (pin "1") (pinfunction "1_1") (pintype "passive"))
    )
    (net (code "118") (name "Net-(E15A-O)") (class "Default")
      (node (ref "E15") (pin "3") (pinfunction "O_3") (pintype "output"))
      (node (ref "E16") (pin "11") (pinfunction "I2_11") (pintype "input"))
      (node (ref "E16") (pin "3") (pinfunction "I0_3") (pintype "input"))
    )
    (net (code "119") (name "Net-(E16A-I1)") (class "Default")
      (node (ref "E16") (pin "2") (pinfunction "I1_2") (pintype "input"))
      (node (ref "E17") (pin "11") (pinfunction "O_11") (pintype "output"))
    )
    (net (code "120") (name "Net-(E16A-O)") (class "Default")
      (node (ref "E16") (pin "12") (pinfunction "O_12") (pintype "output"))
      (node (ref "E19") (pin "14") (pinfunction "CLR_14") (pintype "input"))
      (node (ref "E20") (pin "14") (pinfunction "CLR_14") (pintype "input"))
    )
    (net (code "121") (name "Net-(E16B-O)") (class "Default")
      (node (ref "E16") (pin "6") (pinfunction "O_6") (pintype "output"))
      (node (ref "E19") (pin "5") (pinfunction "UP_5") (pintype "input"))
    )
    (net (code "122") (name "Net-(E16C-O)") (class "Default")
      (node (ref "E16") (pin "8") (pinfunction "O_8") (pintype "output"))
      (node (ref "E19") (pin "4") (pinfunction "DN_4") (pintype "input"))
    )
    (net (code "123") (name "Net-(E17A-I0)") (class "Default")
      (node (ref "E17") (pin "1") (pinfunction "I0_1") (pintype "input"))
      (node (ref "E17") (pin "6") (pinfunction "O_6") (pintype "output"))
    )
    (net (code "124") (name "Net-(E17A-O)") (class "Default")
      (node (ref "E17") (pin "3") (pinfunction "O_3") (pintype "output"))
      (node (ref "E17") (pin "4") (pinfunction "I0_4") (pintype "input"))
      (node (ref "E21") (pin "1") (pinfunction "I0_1") (pintype "input"))
    )
    (net (code "125") (name "Net-(E17C-O)") (class "Default")
      (node (ref "E17") (pin "8") (pinfunction "O_8") (pintype "output"))
      (node (ref "E19") (pin "11") (pinfunction "LD_11") (pintype "input"))
      (node (ref "E20") (pin "11") (pinfunction "LD_11") (pintype "input"))
    )
    (net (code "126") (name "Net-(E19A-BO)") (class "Default")
      (node (ref "E19") (pin "13") (pinfunction "BO_13") (pintype "output"))
      (node (ref "E20") (pin "4") (pinfunction "DN_4") (pintype "input"))
    )
    (net (code "127") (name "Net-(E19A-CO)") (class "Default")
      (node (ref "E19") (pin "12") (pinfunction "CO_12") (pintype "output"))
      (node (ref "E20") (pin "5") (pinfunction "UP_5") (pintype "input"))
    )
    (net (code "128") (name "Net-(E23A-I2)") (class "Default")
      (node (ref "E23") (pin "13") (pinfunction "I2_13") (pintype "input"))
      (node (ref "E23") (pin "8") (pinfunction "O_8") (pintype "output"))
    )
    (net (code "129") (name "Net-(E25-+IN)") (class "Default")
      (node (ref "E25") (pin "3") (pinfunction "+IN_3") (pintype "input"))
      (node (ref "R30") (pin "1") (pinfunction "1_1") (pintype "passive"))
      (node (ref "R31") (pin "2") (pinfunction "2_2") (pintype "passive"))
    )
    (net (code "130") (name "Net-(E25--IN)") (class "Default")
      (node (ref "C38") (pin "1") (pinfunction "1_1") (pintype "passive"))
      (node (ref "E25") (pin "2") (pinfunction "-IN_2") (pintype "input"))
      (node (ref "R29") (pin "1") (pinfunction "1_1") (pintype "passive"))
    )
    (net (code "131") (name "Net-(E25-OUT)") (class "Default")
      (node (ref "E25") (pin "6") (pinfunction "OUT_6") (pintype "output"))
      (node (ref "R29") (pin "2") (pinfunction "2_2") (pintype "passive"))
      (node (ref "R30") (pin "2") (pinfunction "2_2") (pintype "passive"))
      (node (ref "R32") (pin "1") (pinfunction "1_1") (pintype "passive"))
    )
    (net (code "132") (name "Net-(E26A-O)") (class "Default")
      (node (ref "E26") (pin "3") (pinfunction "O_3") (pintype "output"))
      (node (ref "E30") (pin "2") (pinfunction "I1_2") (pintype "input"))
    )
    (net (code "133") (name "Net-(E26B-O)") (class "Default")
      (node (ref "E26") (pin "6") (pinfunction "O_6") (pintype "output"))
      (node (ref "E30") (pin "7") (pinfunction "I1_7") (pintype "input"))
    )
    (net (code "134") (name "Net-(E26C-O)") (class "Default")
      (node (ref "E26") (pin "8") (pinfunction "O_8") (pintype "output"))
      (node (ref "E30") (pin "6") (pinfunction "I0_6") (pintype "input"))
    )
    (net (code "135") (name "Net-(E26D-O)") (class "Default")
      (node (ref "E26") (pin "11") (pinfunction "O_11") (pintype "output"))
      (node (ref "E30") (pin "1") (pinfunction "I0_1") (pintype "input"))
    )
    (net (code "136") (name "Net-(E27A-O)") (class "Default")
      (node (ref "E27") (pin "3") (pinfunction "O_3") (pintype "output"))
      (node (ref "E31") (pin "2") (pinfunction "I1_2") (pintype "input"))
    )
    (net (code "137") (name "Net-(E27B-O)") (class "Default")
      (node (ref "E27") (pin "6") (pinfunction "O_6") (pintype "output"))
      (node (ref "E31") (pin "7") (pinfunction "I1_7") (pintype "input"))
    )
    (net (code "138") (name "Net-(E27C-O)") (class "Default")
      (node (ref "E27") (pin "8") (pinfunction "O_8") (pintype "output"))
      (node (ref "E31") (pin "6") (pinfunction "I0_6") (pintype "input"))
    )
    (net (code "139") (name "Net-(E27D-O)") (class "Default")
      (node (ref "E27") (pin "11") (pinfunction "O_11") (pintype "output"))
      (node (ref "E31") (pin "1") (pinfunction "I0_1") (pintype "input"))
    )
    (net (code "140") (name "Net-(E28A-O)") (class "Default")
      (node (ref "E28") (pin "3") (pinfunction "O_3") (pintype "output"))
      (node (ref "E32") (pin "2") (pinfunction "I1_2") (pintype "input"))
    )
    (net (code "141") (name "Net-(E28B-O)") (class "Default")
      (node (ref "E28") (pin "6") (pinfunction "O_6") (pintype "output"))
      (node (ref "E32") (pin "7") (pinfunction "I1_7") (pintype "input"))
    )
    (net (code "142") (name "Net-(E28C-O)") (class "Default")
      (node (ref "E28") (pin "8") (pinfunction "O_8") (pintype "output"))
      (node (ref "E32") (pin "6") (pinfunction "I0_6") (pintype "input"))
    )
    (net (code "143") (name "Net-(E28D-O)") (class "Default")
      (node (ref "E28") (pin "11") (pinfunction "O_11") (pintype "output"))
      (node (ref "E32") (pin "1") (pinfunction "I0_1") (pintype "input"))
    )
    (net (code "144") (name "Net-(E29A-O)") (class "Default")
      (node (ref "E29") (pin "3") (pinfunction "O_3") (pintype "output"))
      (node (ref "E33") (pin "2") (pinfunction "I1_2") (pintype "input"))
    )
    (net (code "145") (name "Net-(E29B-O)") (class "Default")
      (node (ref "E29") (pin "6") (pinfunction "O_6") (pintype "output"))
      (node (ref "E33") (pin "7") (pinfunction "I1_7") (pintype "input"))
    )
    (net (code "146") (name "Net-(E29C-O)") (class "Default")
      (node (ref "E29") (pin "8") (pinfunction "O_8") (pintype "output"))
      (node (ref "E33") (pin "6") (pinfunction "I0_6") (pintype "input"))
    )
    (net (code "147") (name "Net-(E29D-O)") (class "Default")
      (node (ref "E29") (pin "11") (pinfunction "O_11") (pintype "output"))
      (node (ref "E33") (pin "1") (pinfunction "I0_1") (pintype "input"))
    )
    (net (code "148") (name "Net-(POWER_ON-PadA)") (class "Default")
      (node (ref "POWER_ON") (pin "A") (pinfunction "A_A") (pintype "passive"))
      (node (ref "R3") (pin "1") (pinfunction "1_1") (pintype "passive"))
    )
    (net (code "149") (name "Net-(Q1-PadB1)") (class "Default")
      (node (ref "Q1") (pin "B1") (pinfunction "B1_B1") (pintype "passive"))
      (node (ref "R21") (pin "1") (pinfunction "1_1") (pintype "passive"))
    )
    (net (code "150") (name "Net-(Q1-PadB2)") (class "Default")
      (node (ref "Q1") (pin "B2") (pinfunction "B2_B2") (pintype "passive"))
      (node (ref "R22") (pin "2") (pinfunction "2_2") (pintype "passive"))
    )
    (net (code "151") (name "Net-(R2-Pad1)") (class "Default")
      (node (ref "R2") (pin "1") (pinfunction "1_1") (pintype "passive"))
      (node (ref "SEEK_INC") (pin "A") (pinfunction "A_A") (pintype "passive"))
    )
    (net (code "152") (name "Net-(RTZ-O)") (class "Default")
      (node (ref "RTZ") (pin "1") (pinfunction "O_1") (pintype "passive"))
      (node (ref "RUN") (pin "2") (pinfunction "P_2") (pintype "passive"))
    )
    (net (code "153") (name "OSC_L") (class "Default")
      (node (ref "E16") (pin "13") (pinfunction "I2_13") (pintype "input"))
      (node (ref "FUNCTION") (pin "A3") (pinfunction "A3_A3") (pintype "passive"))
      (node (ref "R35") (pin "1") (pinfunction "1_1") (pintype "passive"))
    )
    (net (code "154") (name "RANDOM_L") (class "Default")
      (node (ref "D1") (pin "C") (pinfunction "C_C") (pintype "passive"))
      (node (ref "E12") (pin "3") (pinfunction "I_3") (pintype "input"))
      (node (ref "FUNCTION") (pin "A4") (pinfunction "A4_A4") (pintype "passive"))
      (node (ref "R34") (pin "1") (pinfunction "1_1") (pintype "passive"))
    )
    (net (code "155") (name "READ_CLOCK") (class "Default")
      (node (ref "J1") (pin "F") (pinfunction "P$2_F") (pintype "bidirectional"))
      (node (ref "RN1") (pin "3") (pinfunction "2_3") (pintype "passive"))
      (node (ref "RN5") (pin "3") (pinfunction "2_3") (pintype "passive"))
    )
    (net (code "156") (name "READ_DATA") (class "Default")
      (node (ref "J1") (pin "D") (pinfunction "P$2_D") (pintype "bidirectional"))
      (node (ref "RN1") (pin "2") (pinfunction "2_2") (pintype "passive"))
      (node (ref "RN5") (pin "2") (pinfunction "2_2") (pintype "passive"))
    )
    (net (code "157") (name "REV_L") (class "Default")
      (node (ref "E16") (pin "5") (pinfunction "I2_5") (pintype "input"))
      (node (ref "E17") (pin "13") (pinfunction "I1_13") (pintype "input"))
      (node (ref "FWD/REV") (pin "1") (pinfunction "O_1") (pintype "passive"))
      (node (ref "R33") (pin "1") (pinfunction "1_1") (pintype "passive"))
    )
    (net (code "158") (name "RK05_AU2") (class "Default")
      (node (ref "J2") (pin "A") (pinfunction "P$2_A") (pintype "bidirectional"))
      (node (ref "RN3") (pin "2") (pinfunction "2_2") (pintype "passive"))
      (node (ref "RN7") (pin "2") (pinfunction "2_2") (pintype "passive"))
    )
    (net (code "159") (name "RK05_BH2") (class "Default")
      (node (ref "J1") (pin "NN") (pinfunction "P$2_NN") (pintype "bidirectional"))
      (node (ref "RN2") (pin "4") (pinfunction "2_4") (pintype "passive"))
      (node (ref "RN6") (pin "4") (pinfunction "2_4") (pintype "passive"))
    )
    (net (code "160") (name "RTZ_L") (class "Default")
      (node (ref "E16") (pin "1") (pinfunction "I0_1") (pintype "input"))
      (node (ref "E17") (pin "2") (pinfunction "I1_2") (pintype "input"))
      (node (ref "E22") (pin "7") (pinfunction "I1_7") (pintype "input"))
      (node (ref "R24") (pin "1") (pinfunction "1_1") (pintype "passive"))
      (node (ref "RTZ") (pin "3") (pinfunction "S_3") (pintype "passive"))
    )
    (net (code "161") (name "RUN_L") (class "Default")
      (node (ref "E13") (pin "2") (pinfunction "I1_2") (pintype "input"))
      (node (ref "R19") (pin "1") (pinfunction "1_1") (pintype "passive"))
      (node (ref "RUN") (pin "1") (pinfunction "O_1") (pintype "passive"))
    )
    (net (code "162") (name "SECTOR_0L") (class "Default")
      (node (ref "E3") (pin "1") (pinfunction "O0_1") (pintype "output"))
      (node (ref "SECTOR") (pin "1") (pinfunction "1_1") (pintype "passive"))
    )
    (net (code "163") (name "SECTOR_1L") (class "Default")
      (node (ref "E3") (pin "2") (pinfunction "O1_2") (pintype "output"))
      (node (ref "SECTOR") (pin "2") (pinfunction "2_2") (pintype "passive"))
    )
    (net (code "164") (name "SECTOR_2L") (class "Default")
      (node (ref "E3") (pin "3") (pinfunction "O2_3") (pintype "output"))
      (node (ref "SECTOR") (pin "3") (pinfunction "3_3") (pintype "passive"))
    )
    (net (code "165") (name "SECTOR_3L") (class "Default")
      (node (ref "E3") (pin "4") (pinfunction "O3_4") (pintype "output"))
      (node (ref "SECTOR") (pin "4") (pinfunction "4_4") (pintype "passive"))
    )
    (net (code "166") (name "SECTOR_4L") (class "Default")
      (node (ref "E3") (pin "5") (pinfunction "O4_5") (pintype "output"))
      (node (ref "SECTOR") (pin "5") (pinfunction "5_5") (pintype "passive"))
    )
    (net (code "167") (name "SECTOR_5L") (class "Default")
      (node (ref "E3") (pin "6") (pinfunction "O5_6") (pintype "output"))
      (node (ref "SECTOR") (pin "6") (pinfunction "6_6") (pintype "passive"))
    )
    (net (code "168") (name "SECTOR_6L") (class "Default")
      (node (ref "E3") (pin "7") (pinfunction "O6_7") (pintype "output"))
      (node (ref "SECTOR") (pin "7") (pinfunction "7_7") (pintype "passive"))
    )
    (net (code "169") (name "SECTOR_7L") (class "Default")
      (node (ref "E3") (pin "9") (pinfunction "O7_9") (pintype "output"))
      (node (ref "SECTOR") (pin "8") (pinfunction "8_8") (pintype "passive"))
    )
    (net (code "170") (name "SECTOR_8L") (class "Default")
      (node (ref "E3") (pin "10") (pinfunction "O8_10") (pintype "output"))
      (node (ref "SECTOR") (pin "9") (pinfunction "9_9") (pintype "passive"))
    )
    (net (code "171") (name "SECTOR_9L") (class "Default")
      (node (ref "E3") (pin "11") (pinfunction "O9_11") (pintype "output"))
      (node (ref "SECTOR") (pin "10") (pinfunction "10_10") (pintype "passive"))
    )
    (net (code "172") (name "SECTOR_SELECT_L") (class "Default")
      (node (ref "E7") (pin "1") (pinfunction "I0_1") (pintype "input"))
      (node (ref "SECTOR") (pin "A") (pinfunction "A_A") (pintype "passive"))
    )
    (net (code "173") (name "SEEK_INCOMPLETE_L") (class "Default")
      (node (ref "E21") (pin "3") (pinfunction "O_3") (pintype "open_collector"))
      (node (ref "SEEK_INC") (pin "B") (pinfunction "B_B") (pintype "passive"))
    )
    (net (code "174") (name "SELECT_0L") (class "Default")
      (node (ref "DRIVE") (pin "A1") (pinfunction "A1_A1") (pintype "passive"))
      (node (ref "J2") (pin "AA") (pinfunction "P$2_AA") (pintype "bidirectional"))
      (node (ref "RN4") (pin "10") (pinfunction "2_10") (pintype "passive"))
      (node (ref "RN8") (pin "10") (pinfunction "2_10") (pintype "passive"))
    )
    (net (code "175") (name "SELECT_1L") (class "Default")
      (node (ref "DRIVE") (pin "A2") (pinfunction "A2_A2") (pintype "passive"))
      (node (ref "J2") (pin "W") (pinfunction "P$2_W") (pintype "bidirectional"))
      (node (ref "R69") (pin "1") (pinfunction "1_1") (pintype "passive"))
      (node (ref "R70") (pin "2") (pinfunction "2_2") (pintype "passive"))
    )
    (net (code "176") (name "SELECT_2L") (class "Default")
      (node (ref "DRIVE") (pin "A3") (pinfunction "A3_A3") (pintype "passive"))
      (node (ref "J2") (pin "S") (pinfunction "P$2_S") (pintype "bidirectional"))
      (node (ref "RN3") (pin "9") (pinfunction "2_9") (pintype "passive"))
      (node (ref "RN7") (pin "9") (pinfunction "2_9") (pintype "passive"))
    )
    (net (code "177") (name "SELECT_3L") (class "Default")
      (node (ref "DRIVE") (pin "A4") (pinfunction "A4_A4") (pintype "passive"))
      (node (ref "J2") (pin "M") (pinfunction "P$2_M") (pintype "bidirectional"))
      (node (ref "RN3") (pin "7") (pinfunction "2_7") (pintype "passive"))
      (node (ref "RN7") (pin "7") (pinfunction "2_7") (pintype "passive"))
    )
    (net (code "178") (name "STEP_L") (class "Default")
      (node (ref "D1") (pin "A") (pinfunction "A_A") (pintype "passive"))
      (node (ref "E18") (pin "1") (pinfunction "CLR_1") (pintype "input"))
      (node (ref "FUNCTION") (pin "A1") (pinfunction "A1_A1") (pintype "passive"))
      (node (ref "R37") (pin "1") (pinfunction "1_1") (pintype "passive"))
    )
    (net (code "179") (name "VCC") (class "Default")
      (node (ref "C1") (pin "1") (pinfunction "1_1") (pintype "passive"))
      (node (ref "C10") (pin "1") (pinfunction "1_1") (pintype "passive"))
      (node (ref "C11") (pin "1") (pinfunction "1_1") (pintype "passive"))
      (node (ref "C12") (pin "1") (pinfunction "1_1") (pintype "passive"))
      (node (ref "C13") (pin "1") (pinfunction "1_1") (pintype "passive"))
      (node (ref "C14") (pin "1") (pinfunction "1_1") (pintype "passive"))
      (node (ref "C15") (pin "1") (pinfunction "1_1") (pintype "passive"))
      (node (ref "C16") (pin "1") (pinfunction "1_1") (pintype "passive"))
      (node (ref "C17") (pin "1") (pinfunction "1_1") (pintype "passive"))
      (node (ref "C18") (pin "1") (pinfunction "1_1") (pintype "passive"))
      (node (ref "C19") (pin "1") (pinfunction "1_1") (pintype "passive"))
      (node (ref "C2") (pin "1") (pinfunction "1_1") (pintype "passive"))
      (node (ref "C20") (pin "1") (pinfunction "1_1") (pintype "passive"))
      (node (ref "C21") (pin "1") (pinfunction "1_1") (pintype "passive"))
      (node (ref "C22") (pin "1") (pinfunction "1_1") (pintype "passive"))
      (node (ref "C23") (pin "1") (pinfunction "1_1") (pintype "passive"))
      (node (ref "C24") (pin "1") (pinfunction "1_1") (pintype "passive"))
      (node (ref "C26") (pin "1") (pinfunction "1_1") (pintype "passive"))
      (node (ref "C27") (pin "1") (pinfunction "1_1") (pintype "passive"))
      (node (ref "C28") (pin "1") (pinfunction "1_1") (pintype "passive"))
      (node (ref "C29") (pin "1") (pinfunction "1_1") (pintype "passive"))
      (node (ref "C3") (pin "1") (pinfunction "1_1") (pintype "passive"))
      (node (ref "C30") (pin "1") (pinfunction "1_1") (pintype "passive"))
      (node (ref "C31") (pin "1") (pinfunction "1_1") (pintype "passive"))
      (node (ref "C32") (pin "1") (pinfunction "1_1") (pintype "passive"))
      (node (ref "C33") (pin "1") (pinfunction "1_1") (pintype "passive"))
      (node (ref "C4") (pin "1") (pinfunction "1_1") (pintype "passive"))
      (node (ref "C40") (pin "1") (pinfunction "1_1") (pintype "passive"))
      (node (ref "C41") (pin "1") (pinfunction "1_1") (pintype "passive"))
      (node (ref "C42") (pin "1") (pinfunction "1_1") (pintype "passive"))
      (node (ref "C43") (pin "1") (pinfunction "1_1") (pintype "passive"))
      (node (ref "C5") (pin "1") (pinfunction "1_1") (pintype "passive"))
      (node (ref "C52") (pin "+") (pinfunction "+_+") (pintype "passive"))
      (node (ref "C6") (pin "1") (pinfunction "1_1") (pintype "passive"))
      (node (ref "C60") (pin "+") (pinfunction "+_+") (pintype "passive"))
      (node (ref "C61") (pin "+") (pinfunction "+_+") (pintype "passive"))
      (node (ref "C67") (pin "+") (pinfunction "+_+") (pintype "passive"))
      (node (ref "C68") (pin "+") (pinfunction "+_+") (pintype "passive"))
      (node (ref "C7") (pin "1") (pinfunction "1_1") (pintype "passive"))
      (node (ref "C8") (pin "1") (pinfunction "1_1") (pintype "passive"))
      (node (ref "C9") (pin "1") (pinfunction "1_1") (pintype "passive"))
      (node (ref "D2") (pin "A") (pinfunction "A_A") (pintype "passive"))
      (node (ref "E5") (pin "1") (pinfunction "CLR_1") (pintype "input"))
      (node (ref "E5") (pin "4") (pinfunction "PRE_4") (pintype "input"))
      (node (ref "POWER") (pin "2") (pinfunction "2_2") (pintype "passive"))
      (node (ref "R10") (pin "2") (pinfunction "2_2") (pintype "passive"))
      (node (ref "R11") (pin "2") (pinfunction "2_2") (pintype "passive"))
      (node (ref "R12") (pin "2") (pinfunction "2_2") (pintype "passive"))
      (node (ref "R13") (pin "2") (pinfunction "2_2") (pintype "passive"))
      (node (ref "R147") (pin "2") (pinfunction "2_2") (pintype "passive"))
      (node (ref "R16") (pin "2") (pinfunction "2_2") (pintype "passive"))
      (node (ref "R17") (pin "2") (pinfunction "2_2") (pintype "passive"))
      (node (ref "R18") (pin "2") (pinfunction "2_2") (pintype "passive"))
      (node (ref "R19") (pin "2") (pinfunction "2_2") (pintype "passive"))
      (node (ref "R24") (pin "2") (pinfunction "2_2") (pintype "passive"))
      (node (ref "R25") (pin "2") (pinfunction "2_2") (pintype "passive"))
      (node (ref "R26") (pin "2") (pinfunction "2_2") (pintype "passive"))
      (node (ref "R27") (pin "2") (pinfunction "2_2") (pintype "passive"))
      (node (ref "R28") (pin "2") (pinfunction "2_2") (pintype "passive"))
      (node (ref "R33") (pin "2") (pinfunction "2_2") (pintype "passive"))
      (node (ref "R34") (pin "2") (pinfunction "2_2") (pintype "passive"))
      (node (ref "R35") (pin "2") (pinfunction "2_2") (pintype "passive"))
      (node (ref "R36") (pin "2") (pinfunction "2_2") (pintype "passive"))
      (node (ref "R37") (pin "2") (pinfunction "2_2") (pintype "passive"))
      (node (ref "R38") (pin "1") (pinfunction "1_1") (pintype "passive"))
      (node (ref "R39") (pin "1") (pinfunction "1_1") (pintype "passive"))
      (node (ref "R4") (pin "2") (pinfunction "2_2") (pintype "passive"))
      (node (ref "R40") (pin "1") (pinfunction "1_1") (pintype "passive"))
      (node (ref "R41") (pin "1") (pinfunction "1_1") (pintype "passive"))
      (node (ref "R42") (pin "1") (pinfunction "1_1") (pintype "passive"))
      (node (ref "R43") (pin "1") (pinfunction "1_1") (pintype "passive"))
      (node (ref "R44") (pin "1") (pinfunction "1_1") (pintype "passive"))
      (node (ref "R45") (pin "1") (pinfunction "1_1") (pintype "passive"))
      (node (ref "R46") (pin "2") (pinfunction "2_2") (pintype "passive"))
      (node (ref "R5") (pin "2") (pinfunction "2_2") (pintype "passive"))
      (node (ref "R50") (pin "2") (pinfunction "2_2") (pintype "passive"))
      (node (ref "R6") (pin "2") (pinfunction "2_2") (pintype "passive"))
      (node (ref "R69") (pin "2") (pinfunction "2_2") (pintype "passive"))
      (node (ref "R7") (pin "2") (pinfunction "2_2") (pintype "passive"))
      (node (ref "R8") (pin "2") (pinfunction "2_2") (pintype "passive"))
      (node (ref "R9") (pin "A") (pinfunction "A_A") (pintype "passive"))
      (node (ref "RN1") (pin "1") (pinfunction "1_1") (pintype "passive"))
      (node (ref "RN2") (pin "1") (pinfunction "1_1") (pintype "passive"))
      (node (ref "RN2") (pin "2") (pinfunction "2_2") (pintype "passive"))
      (node (ref "RN3") (pin "1") (pinfunction "1_1") (pintype "passive"))
      (node (ref "RN4") (pin "1") (pinfunction "1_1") (pintype "passive"))
    )
    (net (code "180") (name "WRITE_GATE") (class "Default")
      (node (ref "E11") (pin "5") (pinfunction "Q_5") (pintype "output"))
      (node (ref "E2") (pin "1") (pinfunction "CLR_1") (pintype "input"))
      (node (ref "E2") (pin "13") (pinfunction "CLR_13") (pintype "input"))
      (node (ref "E5") (pin "13") (pinfunction "CLR_13") (pintype "input"))
      (node (ref "E8") (pin "11") (pinfunction "CLR_11") (pintype "input"))
      (node (ref "E8") (pin "2") (pinfunction "B_2") (pintype "input"))
      (node (ref "E8") (pin "3") (pinfunction "CLR_3") (pintype "input"))
      (node (ref "E9") (pin "11") (pinfunction "I0_11") (pintype "input"))
    )
    (net (code "181") (name "WRITE_H") (class "Default")
      (node (ref "E10") (pin "12") (pinfunction "I0_12") (pintype "input"))
      (node (ref "R5") (pin "1") (pinfunction "1_1") (pintype "passive"))
      (node (ref "WRITE") (pin "1") (pinfunction "O_1") (pintype "passive"))
    )
    (net (code "182") (name "WRITE_L") (class "Default")
      (node (ref "E10") (pin "9") (pinfunction "I0_9") (pintype "input"))
      (node (ref "R6") (pin "1") (pinfunction "1_1") (pintype "passive"))
      (node (ref "WRITE") (pin "3") (pinfunction "S_3") (pintype "passive"))
    )
    (net (code "183") (name "unconnected-(CYL1-O-Pad1)") (class "Default")
      (node (ref "CYL1") (pin "1") (pinfunction "O_1") (pintype "passive"))
    )
    (net (code "184") (name "unconnected-(CYL2-O-Pad1)") (class "Default")
      (node (ref "CYL2") (pin "1") (pinfunction "O_1") (pintype "passive"))
    )
    (net (code "185") (name "unconnected-(CYL4-O-Pad1)") (class "Default")
      (node (ref "CYL4") (pin "1") (pinfunction "O_1") (pintype "passive"))
    )
    (net (code "186") (name "unconnected-(CYL8-O-Pad1)") (class "Default")
      (node (ref "CYL8") (pin "1") (pinfunction "O_1") (pintype "passive"))
    )
    (net (code "187") (name "unconnected-(CYL16-O-Pad1)") (class "Default")
      (node (ref "CYL16") (pin "1") (pinfunction "O_1") (pintype "passive"))
    )
    (net (code "188") (name "unconnected-(CYL32-O-Pad1)") (class "Default")
      (node (ref "CYL32") (pin "1") (pinfunction "O_1") (pintype "passive"))
    )
    (net (code "189") (name "unconnected-(CYL64-O-Pad1)") (class "Default")
      (node (ref "CYL64") (pin "1") (pinfunction "O_1") (pintype "passive"))
    )
    (net (code "190") (name "unconnected-(CYL128-O-Pad1)") (class "Default")
      (node (ref "CYL128") (pin "1") (pinfunction "O_1") (pintype "passive"))
    )
    (net (code "191") (name "unconnected-(DRIVE-PadB)") (class "Default")
      (node (ref "DRIVE") (pin "B") (pinfunction "B_B") (pintype "passive"))
    )
    (net (code "192") (name "unconnected-(DRIVE-PadB1)") (class "Default")
      (node (ref "DRIVE") (pin "B1") (pinfunction "B1_B1") (pintype "passive"))
    )
    (net (code "193") (name "unconnected-(DRIVE-PadB2)") (class "Default")
      (node (ref "DRIVE") (pin "B2") (pinfunction "B2_B2") (pintype "passive"))
    )
    (net (code "194") (name "unconnected-(DRIVE-PadB3)") (class "Default")
      (node (ref "DRIVE") (pin "B3") (pinfunction "B3_B3") (pintype "passive"))
    )
    (net (code "195") (name "unconnected-(DRIVE-PadB4)") (class "Default")
      (node (ref "DRIVE") (pin "B4") (pinfunction "B4_B4") (pintype "passive"))
    )
    (net (code "196") (name "unconnected-(DRIVE-PadC)") (class "Default")
      (node (ref "DRIVE") (pin "C") (pinfunction "C_C") (pintype "passive"))
    )
    (net (code "197") (name "unconnected-(DRIVE-PadC1)") (class "Default")
      (node (ref "DRIVE") (pin "C1") (pinfunction "C1_C1") (pintype "passive"))
    )
    (net (code "198") (name "unconnected-(DRIVE-PadC2)") (class "Default")
      (node (ref "DRIVE") (pin "C2") (pinfunction "C2_C2") (pintype "passive"))
    )
    (net (code "199") (name "unconnected-(DRIVE-PadC3)") (class "Default")
      (node (ref "DRIVE") (pin "C3") (pinfunction "C3_C3") (pintype "passive"))
    )
    (net (code "200") (name "unconnected-(DRIVE-PadC4)") (class "Default")
      (node (ref "DRIVE") (pin "C4") (pinfunction "C4_C4") (pintype "passive"))
    )
    (net (code "201") (name "unconnected-(E5A-Q-Pad5)") (class "Default")
      (node (ref "E5") (pin "5") (pinfunction "Q_5") (pintype "output"))
    )
    (net (code "202") (name "unconnected-(E5A-~{Q}-Pad6)") (class "Default")
      (node (ref "E5") (pin "6") (pinfunction "~{Q}_6") (pintype "output"))
    )
    (net (code "203") (name "unconnected-(E5B-Q-Pad9)") (class "Default")
      (node (ref "E5") (pin "9") (pinfunction "Q_9") (pintype "output"))
    )
    (net (code "204") (name "unconnected-(E8A-Q-Pad13)") (class "Default")
      (node (ref "E8") (pin "13") (pinfunction "Q_13") (pintype "output"))
    )
    (net (code "205") (name "unconnected-(E9A-O-Pad1)") (class "Default")
      (node (ref "E9") (pin "1") (pinfunction "O_1") (pintype "open_collector"))
    )
    (net (code "206") (name "unconnected-(E9B-O-Pad4)") (class "Default")
      (node (ref "E9") (pin "4") (pinfunction "O_4") (pintype "open_collector"))
    )
    (net (code "207") (name "unconnected-(E10A-O-Pad3)") (class "Default")
      (node (ref "E10") (pin "3") (pinfunction "O_3") (pintype "output"))
    )
    (net (code "208") (name "unconnected-(E10B-O-Pad6)") (class "Default")
      (node (ref "E10") (pin "6") (pinfunction "O_6") (pintype "output"))
    )
    (net (code "209") (name "unconnected-(E11A-~{Q}-Pad6)") (class "Default")
      (node (ref "E11") (pin "6") (pinfunction "~{Q}_6") (pintype "output"))
    )
    (net (code "210") (name "unconnected-(E11B-~{Q}-Pad8)") (class "Default")
      (node (ref "E11") (pin "8") (pinfunction "~{Q}_8") (pintype "output"))
    )
    (net (code "211") (name "unconnected-(E14A-Q-Pad13)") (class "Default")
      (node (ref "E14") (pin "13") (pinfunction "Q_13") (pintype "output"))
    )
    (net (code "212") (name "unconnected-(E14B-Q-Pad5)") (class "Default")
      (node (ref "E14") (pin "5") (pinfunction "Q_5") (pintype "output"))
    )
    (net (code "213") (name "unconnected-(E15B-O-Pad6)") (class "Default")
      (node (ref "E15") (pin "6") (pinfunction "O_6") (pintype "output"))
    )
    (net (code "214") (name "unconnected-(E15C-O-Pad8)") (class "Default")
      (node (ref "E15") (pin "8") (pinfunction "O_8") (pintype "output"))
    )
    (net (code "215") (name "unconnected-(E15D-O-Pad11)") (class "Default")
      (node (ref "E15") (pin "11") (pinfunction "O_11") (pintype "output"))
    )
    (net (code "216") (name "unconnected-(E18B-Q-Pad9)") (class "Default")
      (node (ref "E18") (pin "9") (pinfunction "Q_9") (pintype "output"))
    )
    (net (code "217") (name "unconnected-(E18B-~{Q}-Pad8)") (class "Default")
      (node (ref "E18") (pin "8") (pinfunction "~{Q}_8") (pintype "output"))
    )
    (net (code "218") (name "unconnected-(E20A-BO-Pad13)") (class "Default")
      (node (ref "E20") (pin "13") (pinfunction "BO_13") (pintype "output"))
    )
    (net (code "219") (name "unconnected-(E20A-CO-Pad12)") (class "Default")
      (node (ref "E20") (pin "12") (pinfunction "CO_12") (pintype "output"))
    )
    (net (code "220") (name "unconnected-(E24B-O-Pad8)") (class "Default")
      (node (ref "E24") (pin "8") (pinfunction "O_8") (pintype "output"))
    )
    (net (code "221") (name "unconnected-(E25-ON1-Pad1)") (class "Default")
      (node (ref "E25") (pin "1") (pinfunction "ON1_1") (pintype "passive"))
    )
    (net (code "222") (name "unconnected-(E25-ON2-Pad5)") (class "Default")
      (node (ref "E25") (pin "5") (pinfunction "ON2_5") (pintype "passive"))
    )
    (net (code "223") (name "unconnected-(E25-OPT-Pad8)") (class "Default")
      (node (ref "E25") (pin "8") (pinfunction "OPT_8") (pintype "passive"))
    )
    (net (code "224") (name "unconnected-(FUNCTION-PadA2)") (class "Default")
      (node (ref "FUNCTION") (pin "A2") (pinfunction "A2_A2") (pintype "passive"))
    )
    (net (code "225") (name "unconnected-(FUNCTION-PadB)") (class "Default")
      (node (ref "FUNCTION") (pin "B") (pinfunction "B_B") (pintype "passive"))
    )
    (net (code "226") (name "unconnected-(FUNCTION-PadB1)") (class "Default")
      (node (ref "FUNCTION") (pin "B1") (pinfunction "B1_B1") (pintype "passive"))
    )
    (net (code "227") (name "unconnected-(FUNCTION-PadB2)") (class "Default")
      (node (ref "FUNCTION") (pin "B2") (pinfunction "B2_B2") (pintype "passive"))
    )
    (net (code "228") (name "unconnected-(FUNCTION-PadB3)") (class "Default")
      (node (ref "FUNCTION") (pin "B3") (pinfunction "B3_B3") (pintype "passive"))
    )
    (net (code "229") (name "unconnected-(FUNCTION-PadB4)") (class "Default")
      (node (ref "FUNCTION") (pin "B4") (pinfunction "B4_B4") (pintype "passive"))
    )
    (net (code "230") (name "unconnected-(FUNCTION-PadC)") (class "Default")
      (node (ref "FUNCTION") (pin "C") (pinfunction "C_C") (pintype "passive"))
    )
    (net (code "231") (name "unconnected-(FUNCTION-PadC1)") (class "Default")
      (node (ref "FUNCTION") (pin "C1") (pinfunction "C1_C1") (pintype "passive"))
    )
    (net (code "232") (name "unconnected-(FUNCTION-PadC2)") (class "Default")
      (node (ref "FUNCTION") (pin "C2") (pinfunction "C2_C2") (pintype "passive"))
    )
    (net (code "233") (name "unconnected-(FUNCTION-PadC3)") (class "Default")
      (node (ref "FUNCTION") (pin "C3") (pinfunction "C3_C3") (pintype "passive"))
    )
    (net (code "234") (name "unconnected-(FUNCTION-PadC4)") (class "Default")
      (node (ref "FUNCTION") (pin "C4") (pinfunction "C4_C4") (pintype "passive"))
    )
    (net (code "235") (name "unconnected-(HEAD-O-Pad1)") (class "Default")
      (node (ref "HEAD") (pin "1") (pinfunction "O_1") (pintype "passive"))
    )
    (net (code "236") (name "unconnected-(RUN-S-Pad3)") (class "Default")
      (node (ref "RUN") (pin "3") (pinfunction "S_3") (pintype "passive"))
    )
  )
)
